# 8x2AND_OR_1.net
KiCad netlist of a schematic drawn in EAGLE
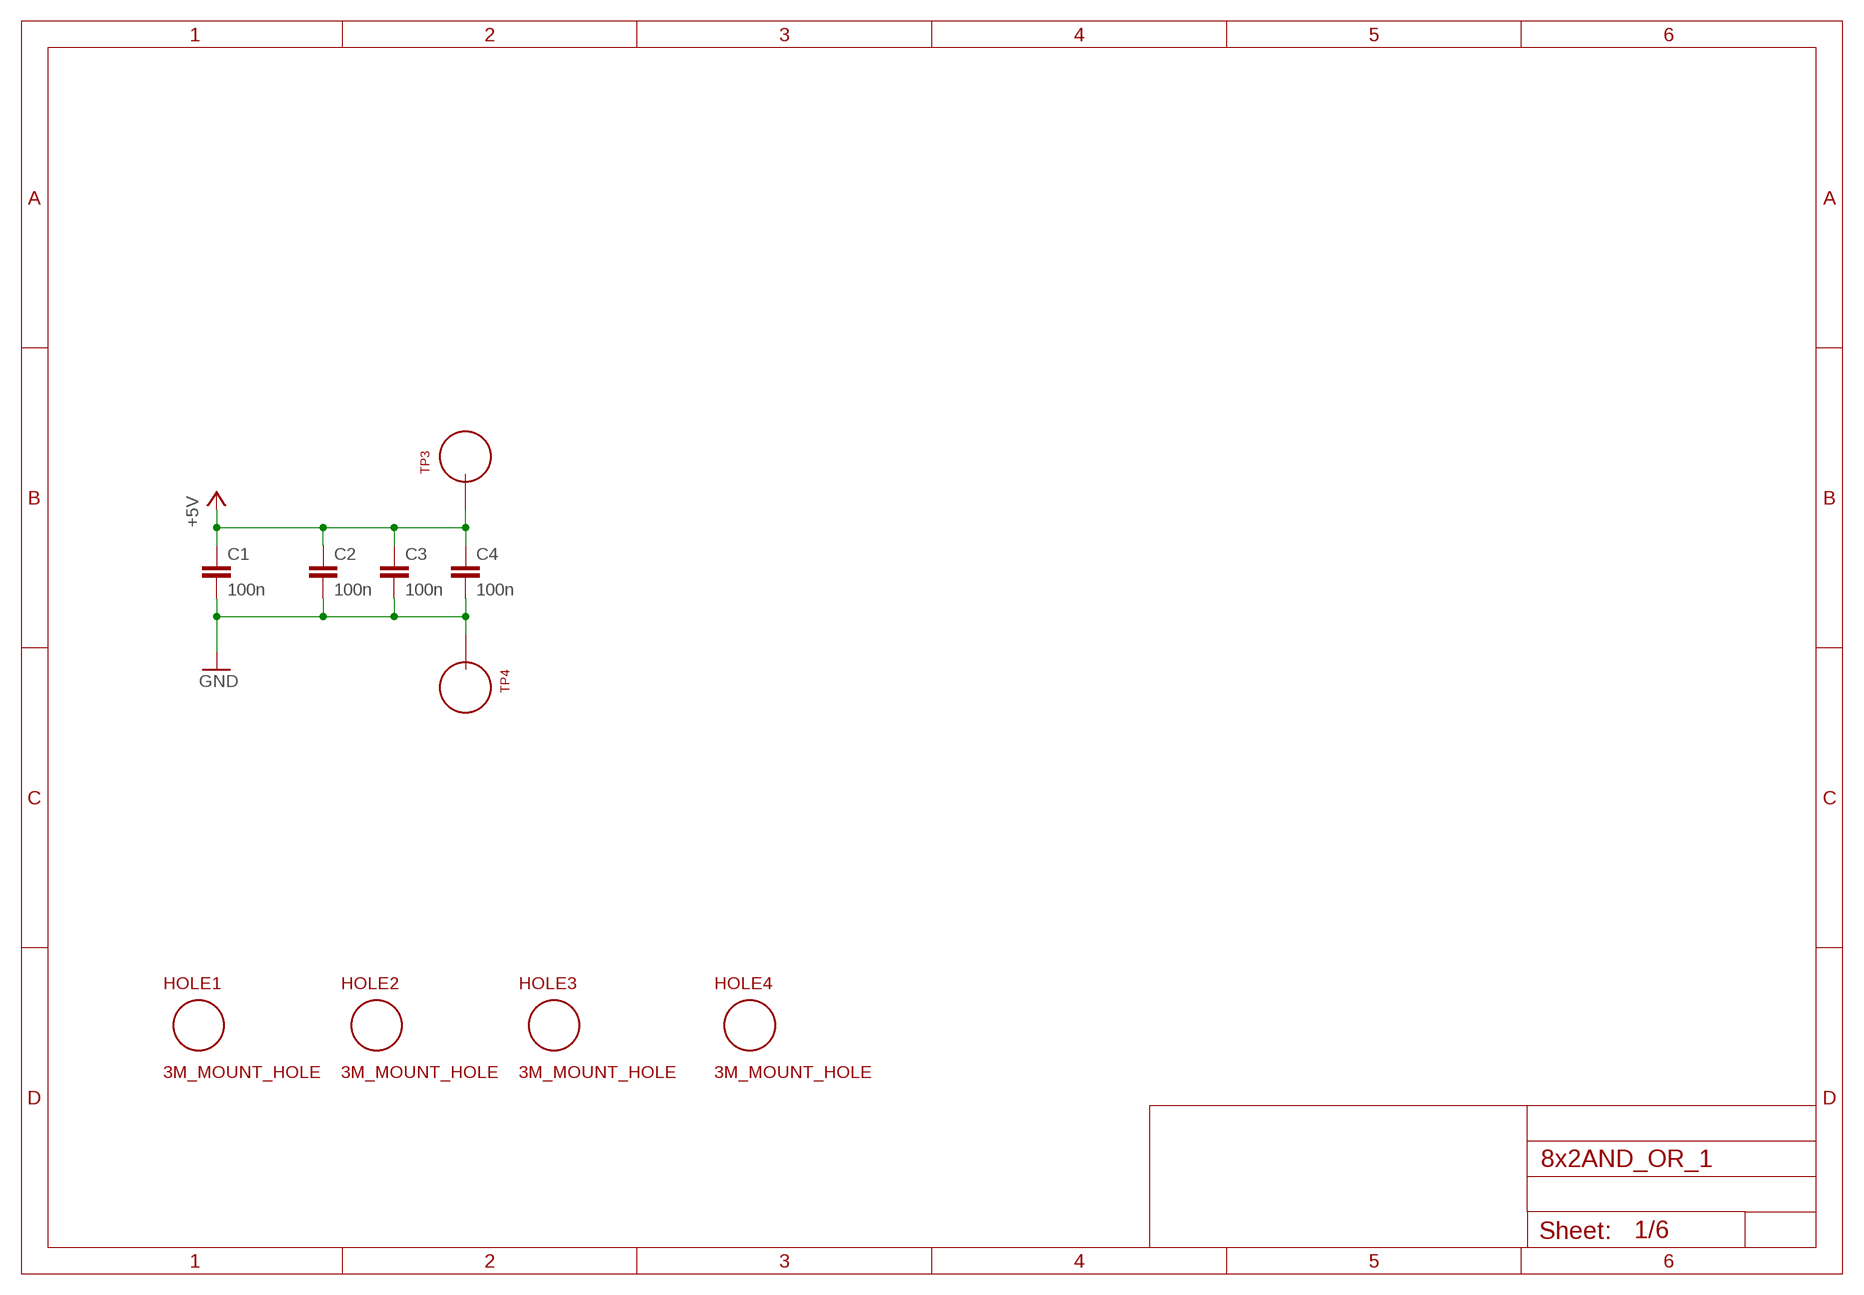
[diagram p0: schematic, sheet 1]
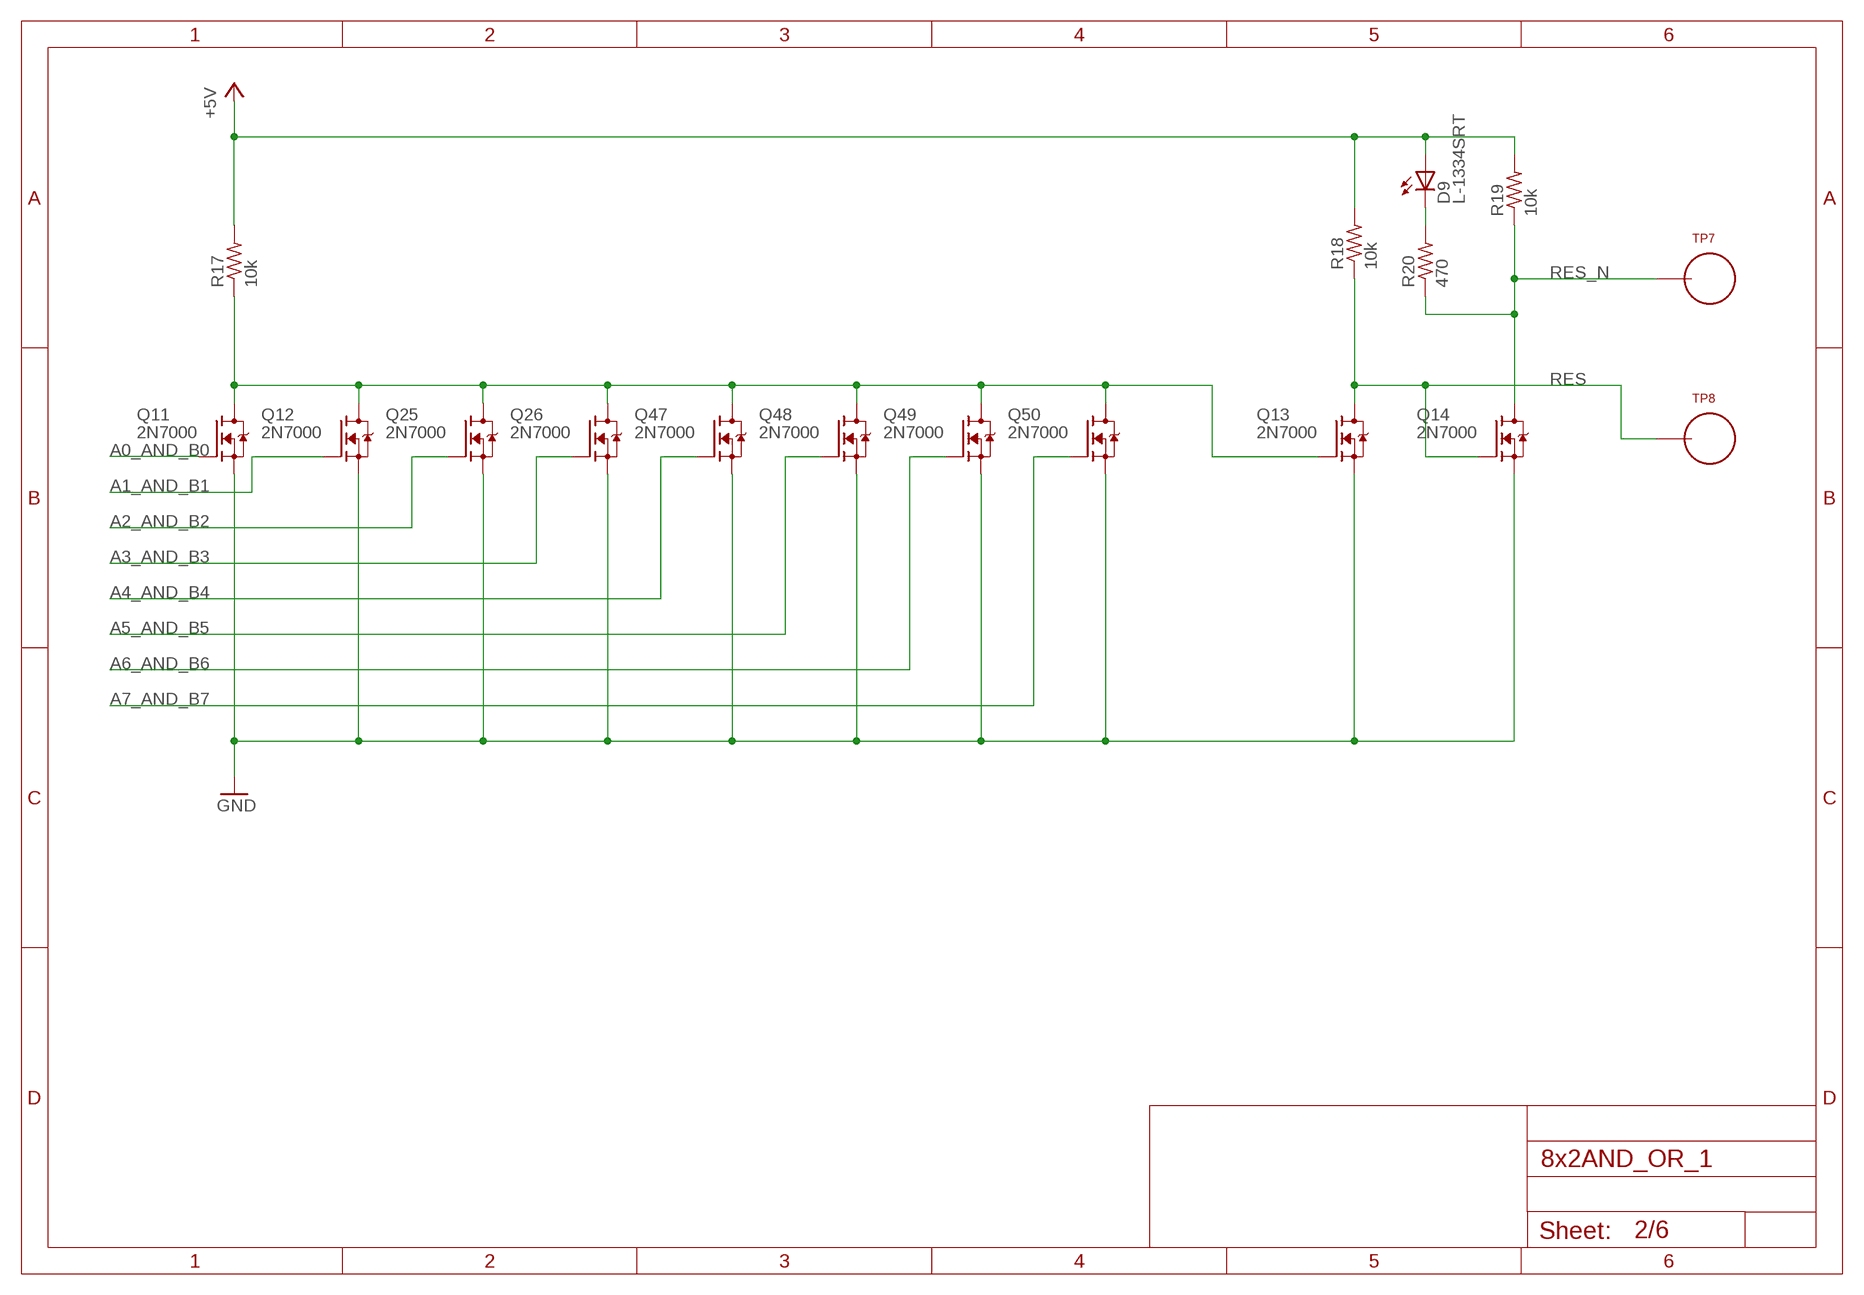
[diagram p1: schematic, sheet 2]
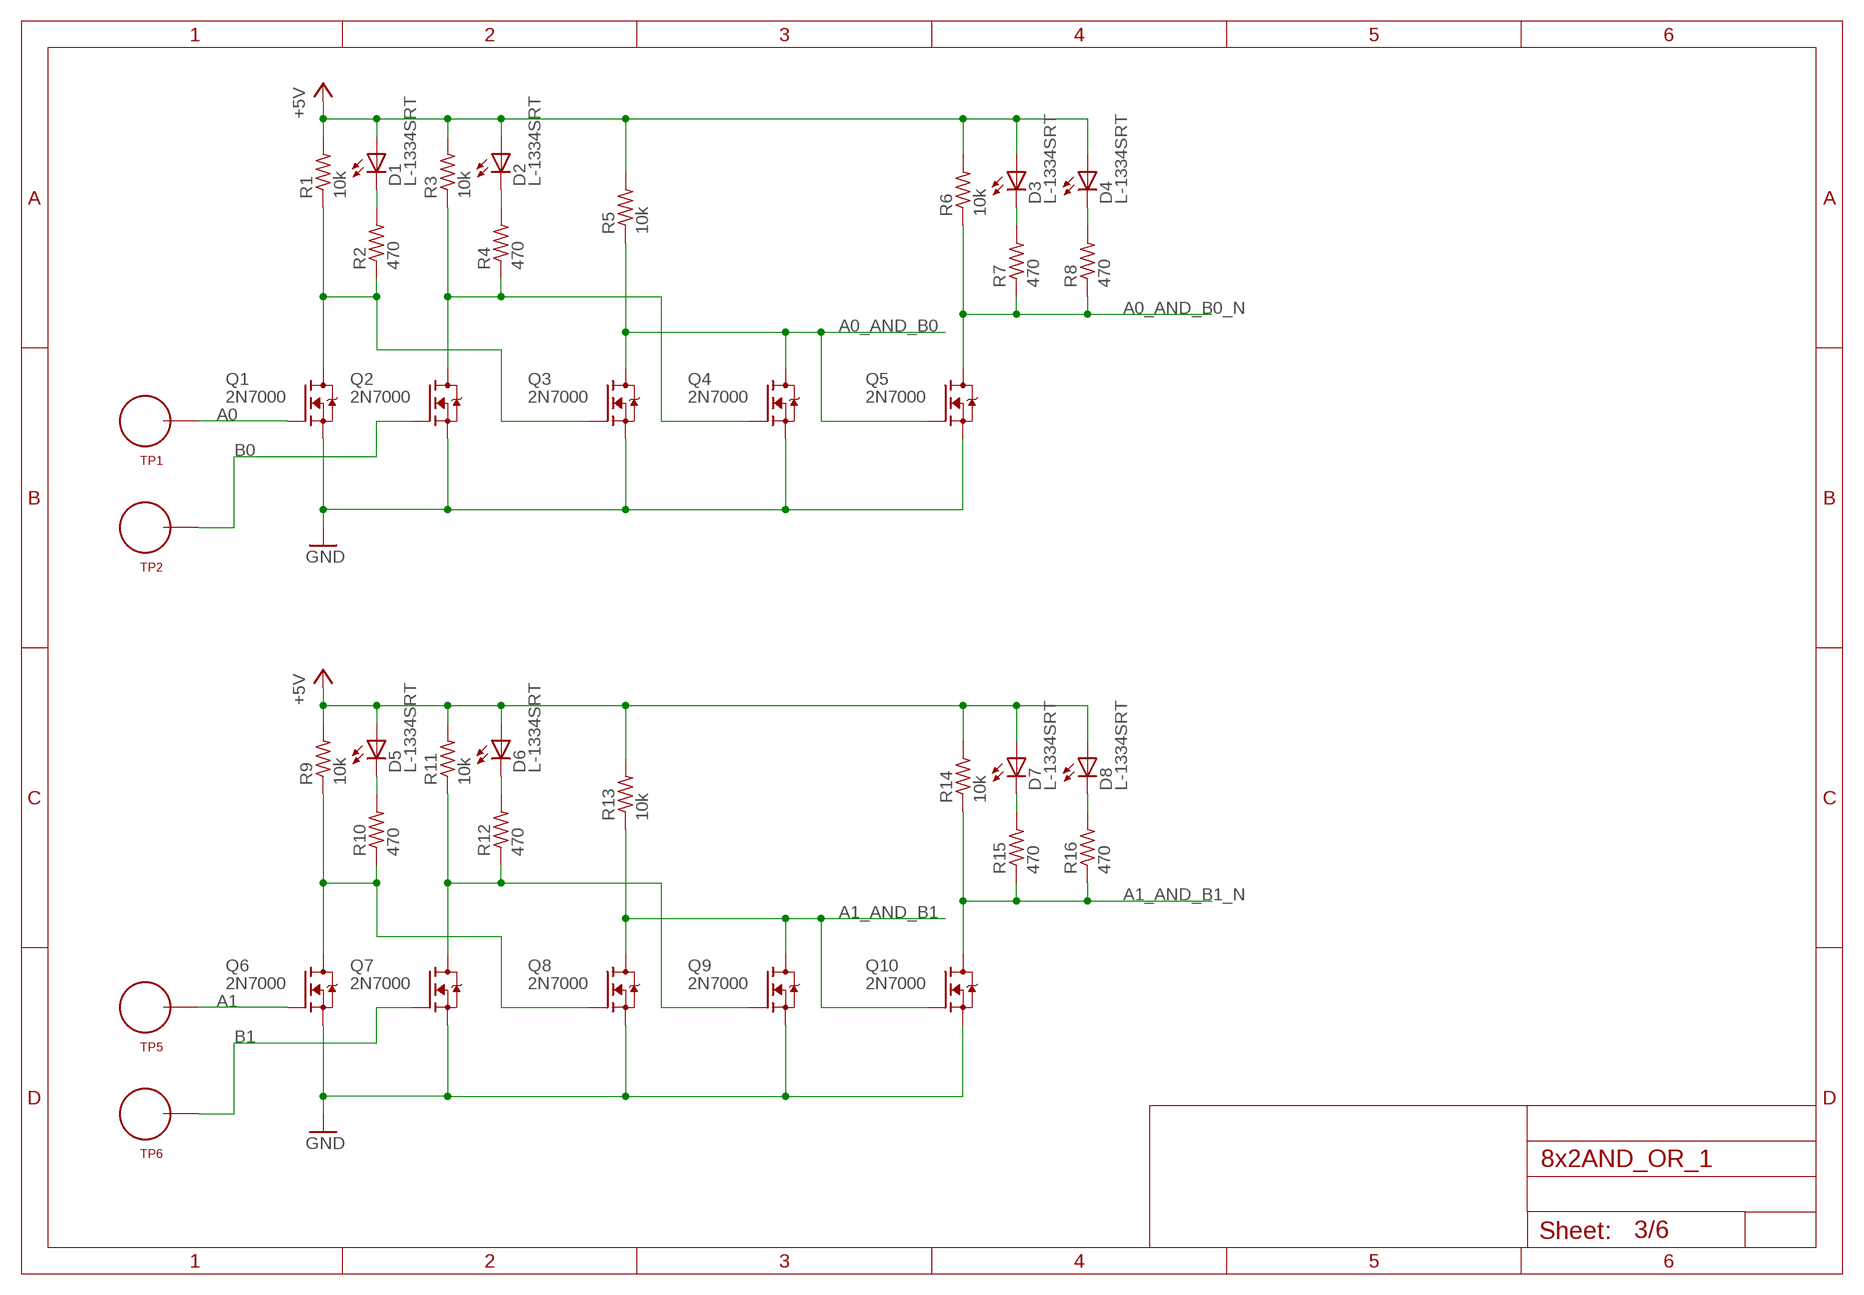
[diagram p2: schematic, sheet 3]
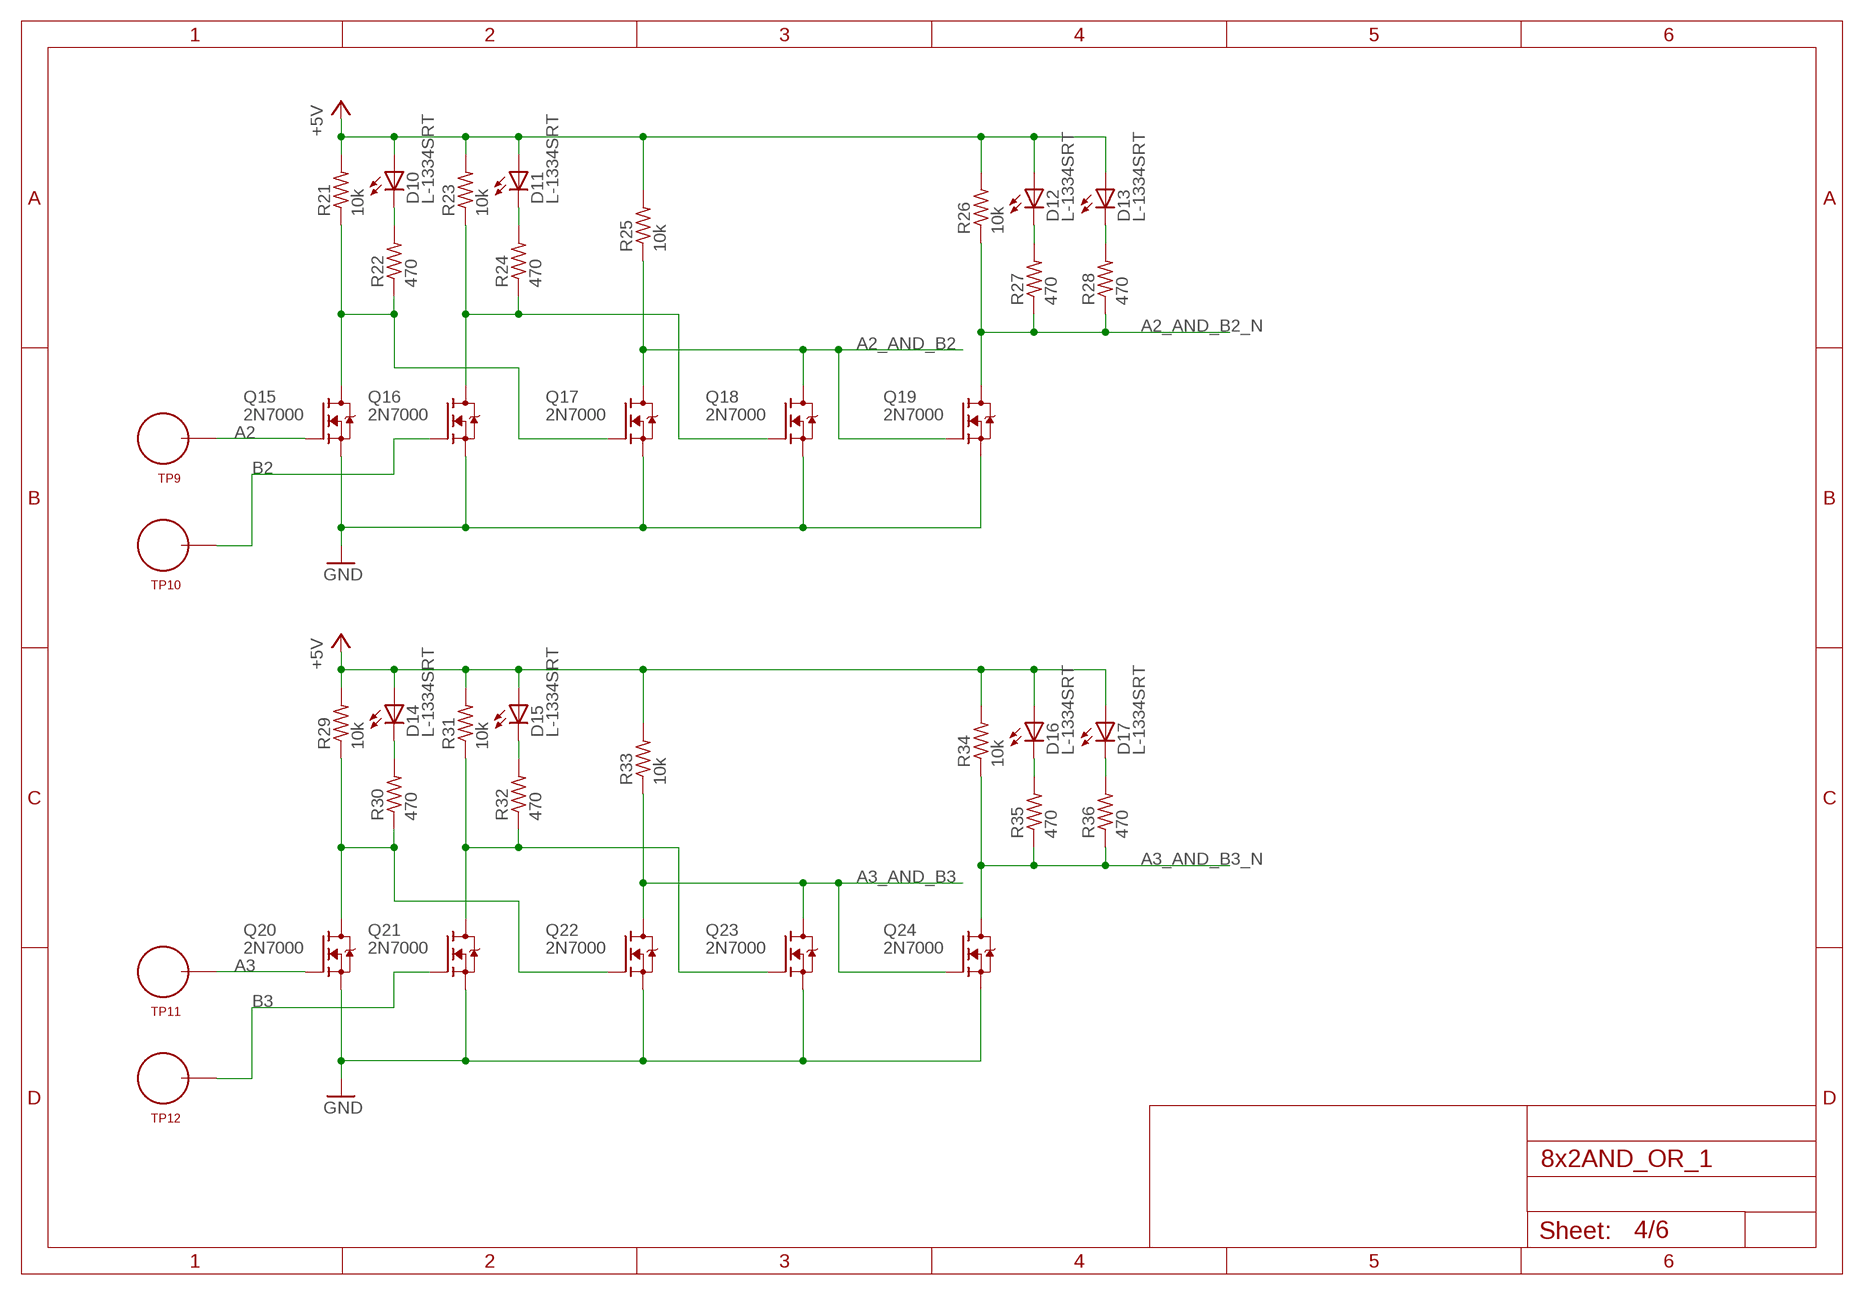
[diagram p3: schematic, sheet 4]
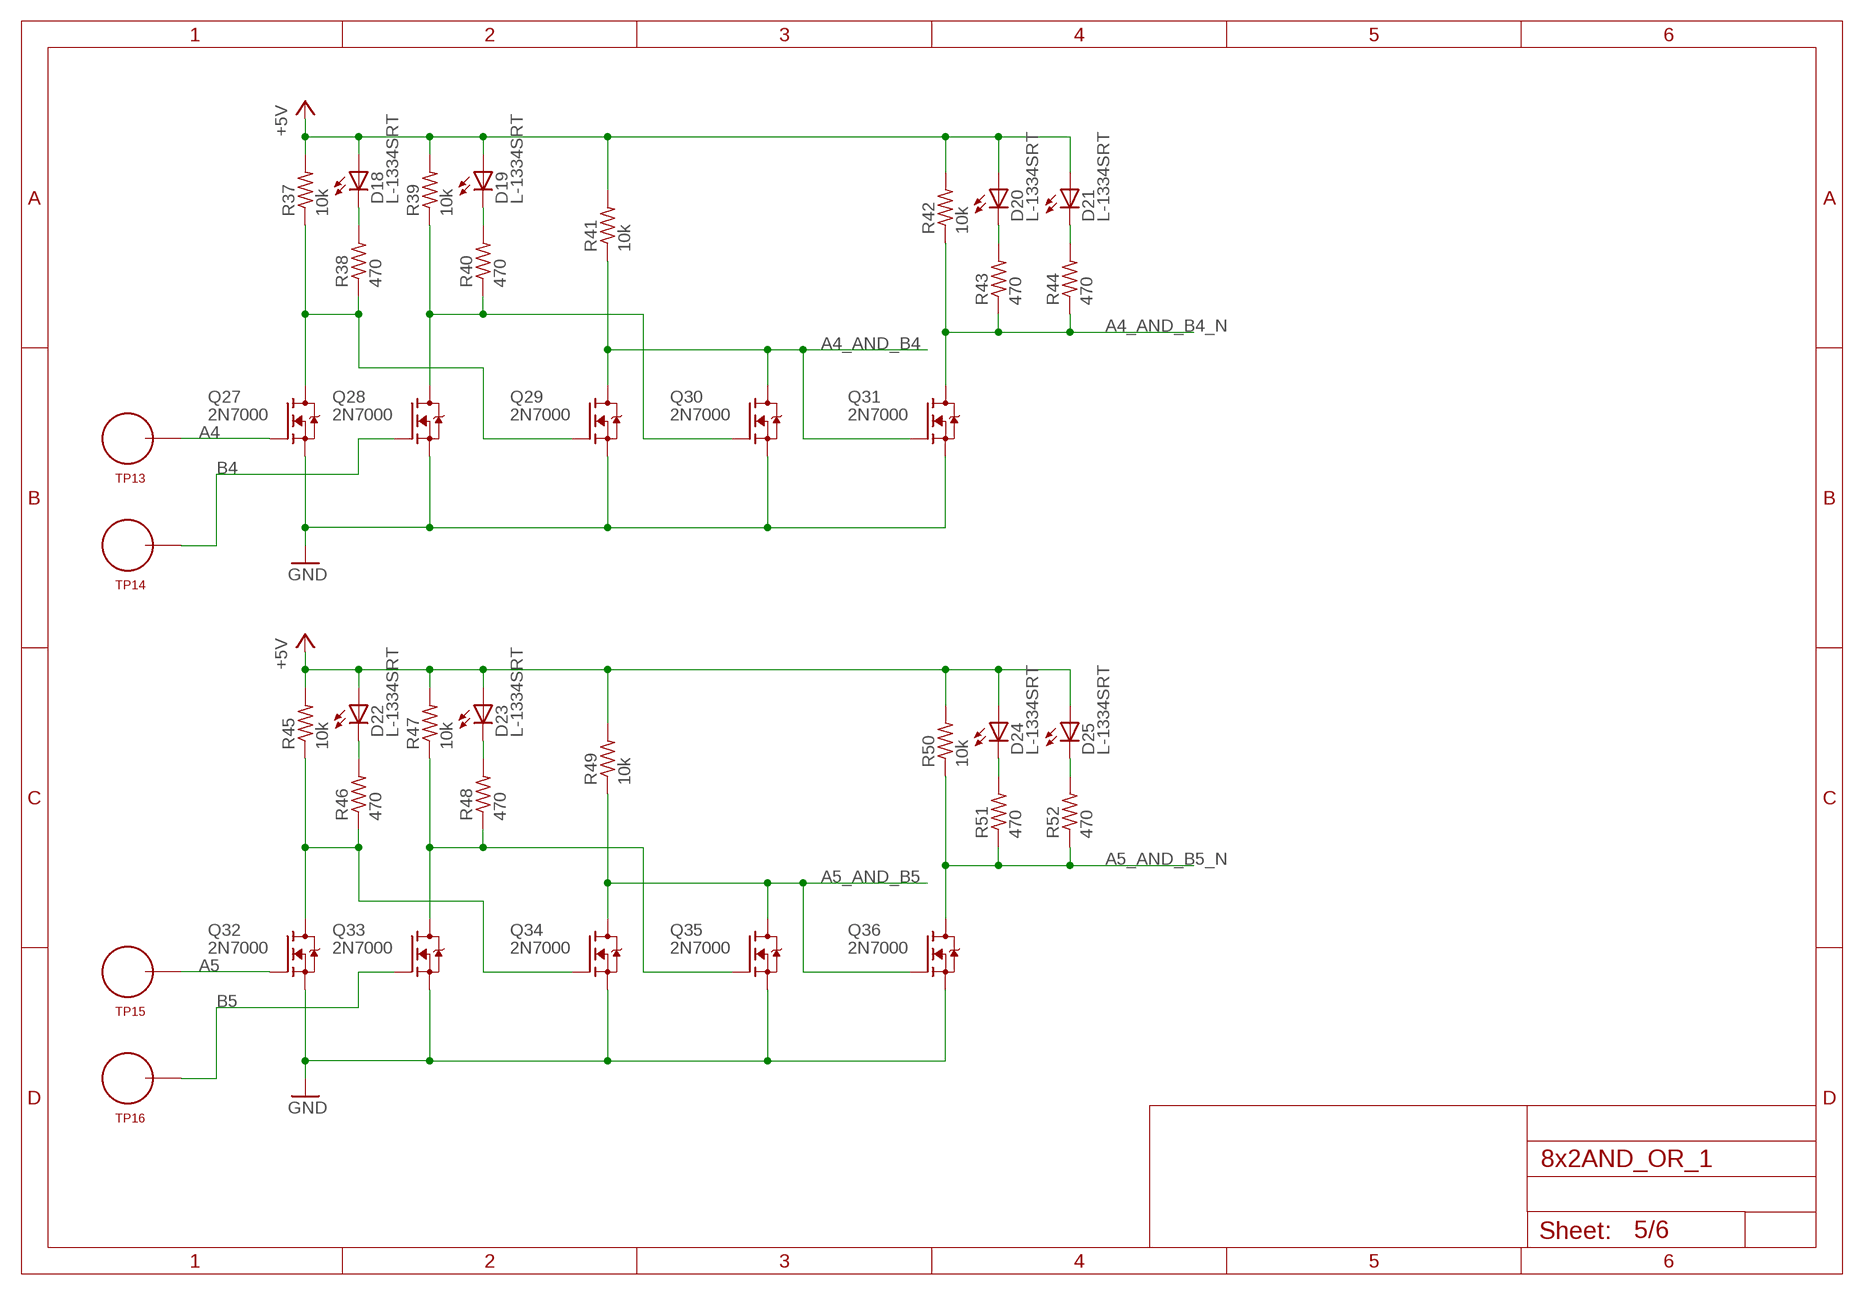
[diagram p4: schematic, sheet 5]
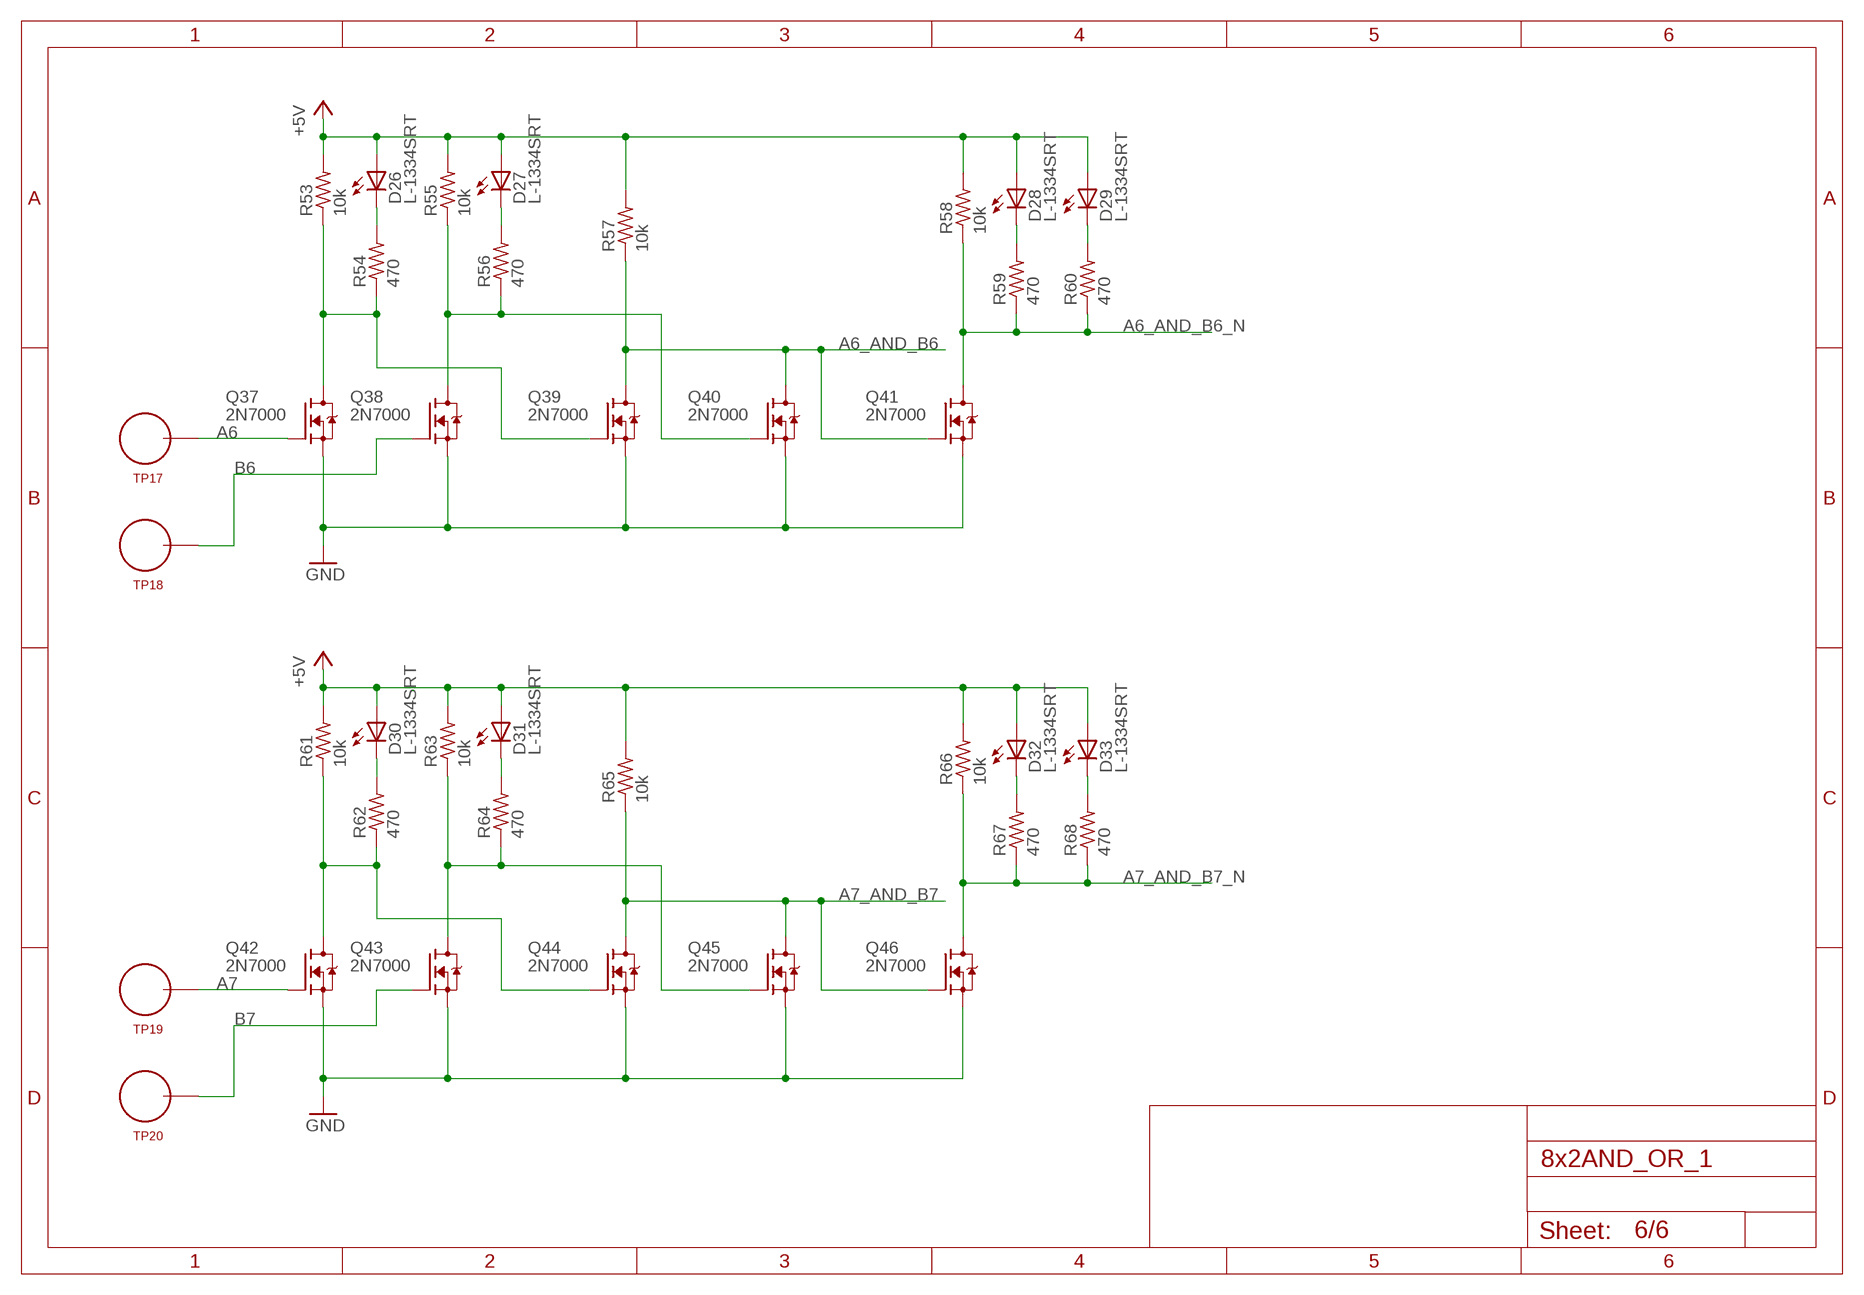
[diagram p5: schematic, sheet 6]

(export (version "E")
  (design (tool "Eeschema 10.0.6"))
  (components
    (comp (ref "D18")
      (value "L-1334SRT")
      (footprint "eagle-import:LED3MM")
      (libsource (lib "eagle-import") (part "L-1334SRT"))
    )
    (comp (ref "D19")
      (value "L-1334SRT")
      (footprint "eagle-import:LED3MM")
      (libsource (lib "eagle-import") (part "L-1334SRT"))
    )
    (comp (ref "D20")
      (value "L-1334SRT")
      (footprint "eagle-import:LED3MM")
      (libsource (lib "eagle-import") (part "L-1334SRT"))
    )
    (comp (ref "D21")
      (value "L-1334SRT")
      (footprint "eagle-import:LED3MM")
      (libsource (lib "eagle-import") (part "L-1334SRT"))
    )
    (comp (ref "D22")
      (value "L-1334SRT")
      (footprint "eagle-import:LED3MM")
      (libsource (lib "eagle-import") (part "L-1334SRT"))
    )
    (comp (ref "D23")
      (value "L-1334SRT")
      (footprint "eagle-import:LED3MM")
      (libsource (lib "eagle-import") (part "L-1334SRT"))
    )
    (comp (ref "D24")
      (value "L-1334SRT")
      (footprint "eagle-import:LED3MM")
      (libsource (lib "eagle-import") (part "L-1334SRT"))
    )
    (comp (ref "D25")
      (value "L-1334SRT")
      (footprint "eagle-import:LED3MM")
      (libsource (lib "eagle-import") (part "L-1334SRT"))
    )
    (comp (ref "Q27")
      (value "2N7000")
      (footprint "eagle-import:TO92-DGS")
      (libsource (lib "eagle-import") (part "2N7000"))
    )
    (comp (ref "Q28")
      (value "2N7000")
      (footprint "eagle-import:TO92-DGS")
      (libsource (lib "eagle-import") (part "2N7000"))
    )
    (comp (ref "Q29")
      (value "2N7000")
      (footprint "eagle-import:TO92-DGS")
      (libsource (lib "eagle-import") (part "2N7000"))
    )
    (comp (ref "Q30")
      (value "2N7000")
      (footprint "eagle-import:TO92-DGS")
      (libsource (lib "eagle-import") (part "2N7000"))
    )
    (comp (ref "Q31")
      (value "2N7000")
      (footprint "eagle-import:TO92-DGS")
      (libsource (lib "eagle-import") (part "2N7000"))
    )
    (comp (ref "Q32")
      (value "2N7000")
      (footprint "eagle-import:TO92-DGS")
      (libsource (lib "eagle-import") (part "2N7000"))
    )
    (comp (ref "Q33")
      (value "2N7000")
      (footprint "eagle-import:TO92-DGS")
      (libsource (lib "eagle-import") (part "2N7000"))
    )
    (comp (ref "Q34")
      (value "2N7000")
      (footprint "eagle-import:TO92-DGS")
      (libsource (lib "eagle-import") (part "2N7000"))
    )
    (comp (ref "Q35")
      (value "2N7000")
      (footprint "eagle-import:TO92-DGS")
      (libsource (lib "eagle-import") (part "2N7000"))
    )
    (comp (ref "Q36")
      (value "2N7000")
      (footprint "eagle-import:TO92-DGS")
      (libsource (lib "eagle-import") (part "2N7000"))
    )
    (comp (ref "R37")
      (value "10k")
      (footprint "eagle-import:R_P2INCH")
      (libsource (lib "eagle-import") (part "R_P2INCH"))
    )
    (comp (ref "R38")
      (value "470")
      (footprint "eagle-import:R_P2INCH")
      (libsource (lib "eagle-import") (part "R_P2INCH"))
    )
    (comp (ref "R39")
      (value "10k")
      (footprint "eagle-import:R_P2INCH")
      (libsource (lib "eagle-import") (part "R_P2INCH"))
    )
    (comp (ref "R40")
      (value "470")
      (footprint "eagle-import:R_P2INCH")
      (libsource (lib "eagle-import") (part "R_P2INCH"))
    )
    (comp (ref "R41")
      (value "10k")
      (footprint "eagle-import:R_P2INCH")
      (libsource (lib "eagle-import") (part "R_P2INCH"))
    )
    (comp (ref "R42")
      (value "10k")
      (footprint "eagle-import:R_P2INCH")
      (libsource (lib "eagle-import") (part "R_P2INCH"))
    )
    (comp (ref "R43")
      (value "470")
      (footprint "eagle-import:R_P2INCH")
      (libsource (lib "eagle-import") (part "R_P2INCH"))
    )
    (comp (ref "R44")
      (value "470")
      (footprint "eagle-import:R_P2INCH")
      (libsource (lib "eagle-import") (part "R_P2INCH"))
    )
    (comp (ref "R45")
      (value "10k")
      (footprint "eagle-import:R_P2INCH")
      (libsource (lib "eagle-import") (part "R_P2INCH"))
    )
    (comp (ref "R46")
      (value "470")
      (footprint "eagle-import:R_P2INCH")
      (libsource (lib "eagle-import") (part "R_P2INCH"))
    )
    (comp (ref "R47")
      (value "10k")
      (footprint "eagle-import:R_P2INCH")
      (libsource (lib "eagle-import") (part "R_P2INCH"))
    )
    (comp (ref "R48")
      (value "470")
      (footprint "eagle-import:R_P2INCH")
      (libsource (lib "eagle-import") (part "R_P2INCH"))
    )
    (comp (ref "R49")
      (value "10k")
      (footprint "eagle-import:R_P2INCH")
      (libsource (lib "eagle-import") (part "R_P2INCH"))
    )
    (comp (ref "R50")
      (value "10k")
      (footprint "eagle-import:R_P2INCH")
      (libsource (lib "eagle-import") (part "R_P2INCH"))
    )
    (comp (ref "R51")
      (value "470")
      (footprint "eagle-import:R_P2INCH")
      (libsource (lib "eagle-import") (part "R_P2INCH"))
    )
    (comp (ref "R52")
      (value "470")
      (footprint "eagle-import:R_P2INCH")
      (libsource (lib "eagle-import") (part "R_P2INCH"))
    )
    (comp (ref "TP13")
      (value "TEST_LOOP")
      (footprint "eagle-import:TEST_LOOP")
      (libsource (lib "eagle-import") (part "TEST_LOOP"))
    )
    (comp (ref "TP14")
      (value "TEST_LOOP")
      (footprint "eagle-import:TEST_LOOP")
      (libsource (lib "eagle-import") (part "TEST_LOOP"))
    )
    (comp (ref "TP15")
      (value "TEST_LOOP")
      (footprint "eagle-import:TEST_LOOP")
      (libsource (lib "eagle-import") (part "TEST_LOOP"))
    )
    (comp (ref "TP16")
      (value "TEST_LOOP")
      (footprint "eagle-import:TEST_LOOP")
      (libsource (lib "eagle-import") (part "TEST_LOOP"))
    )
    (comp (ref "D9")
      (value "L-1334SRT")
      (footprint "eagle-import:LED3MM")
      (libsource (lib "eagle-import") (part "L-1334SRT"))
    )
    (comp (ref "Q11")
      (value "2N7000")
      (footprint "eagle-import:TO92-DGS")
      (libsource (lib "eagle-import") (part "2N7000"))
    )
    (comp (ref "Q12")
      (value "2N7000")
      (footprint "eagle-import:TO92-DGS")
      (libsource (lib "eagle-import") (part "2N7000"))
    )
    (comp (ref "Q13")
      (value "2N7000")
      (footprint "eagle-import:TO92-DGS")
      (libsource (lib "eagle-import") (part "2N7000"))
    )
    (comp (ref "Q14")
      (value "2N7000")
      (footprint "eagle-import:TO92-DGS")
      (libsource (lib "eagle-import") (part "2N7000"))
    )
    (comp (ref "Q25")
      (value "2N7000")
      (footprint "eagle-import:TO92-DGS")
      (libsource (lib "eagle-import") (part "2N7000"))
    )
    (comp (ref "Q26")
      (value "2N7000")
      (footprint "eagle-import:TO92-DGS")
      (libsource (lib "eagle-import") (part "2N7000"))
    )
    (comp (ref "Q47")
      (value "2N7000")
      (footprint "eagle-import:TO92-DGS")
      (libsource (lib "eagle-import") (part "2N7000"))
    )
    (comp (ref "Q48")
      (value "2N7000")
      (footprint "eagle-import:TO92-DGS")
      (libsource (lib "eagle-import") (part "2N7000"))
    )
    (comp (ref "Q49")
      (value "2N7000")
      (footprint "eagle-import:TO92-DGS")
      (libsource (lib "eagle-import") (part "2N7000"))
    )
    (comp (ref "Q50")
      (value "2N7000")
      (footprint "eagle-import:TO92-DGS")
      (libsource (lib "eagle-import") (part "2N7000"))
    )
    (comp (ref "R17")
      (value "10k")
      (footprint "eagle-import:R_P2INCH")
      (libsource (lib "eagle-import") (part "R_P2INCH"))
    )
    (comp (ref "R18")
      (value "10k")
      (footprint "eagle-import:R_P2INCH")
      (libsource (lib "eagle-import") (part "R_P2INCH"))
    )
    (comp (ref "R19")
      (value "10k")
      (footprint "eagle-import:R_P2INCH")
      (libsource (lib "eagle-import") (part "R_P2INCH"))
    )
    (comp (ref "R20")
      (value "470")
      (footprint "eagle-import:R_P2INCH")
      (libsource (lib "eagle-import") (part "R_P2INCH"))
    )
    (comp (ref "TP7")
      (value "TEST_LOOP")
      (footprint "eagle-import:TEST_LOOP")
      (libsource (lib "eagle-import") (part "TEST_LOOP"))
    )
    (comp (ref "TP8")
      (value "TEST_LOOP")
      (footprint "eagle-import:TEST_LOOP")
      (libsource (lib "eagle-import") (part "TEST_LOOP"))
    )
    (comp (ref "D10")
      (value "L-1334SRT")
      (footprint "eagle-import:LED3MM")
      (libsource (lib "eagle-import") (part "L-1334SRT"))
    )
    (comp (ref "D11")
      (value "L-1334SRT")
      (footprint "eagle-import:LED3MM")
      (libsource (lib "eagle-import") (part "L-1334SRT"))
    )
    (comp (ref "D12")
      (value "L-1334SRT")
      (footprint "eagle-import:LED3MM")
      (libsource (lib "eagle-import") (part "L-1334SRT"))
    )
    (comp (ref "D13")
      (value "L-1334SRT")
      (footprint "eagle-import:LED3MM")
      (libsource (lib "eagle-import") (part "L-1334SRT"))
    )
    (comp (ref "D14")
      (value "L-1334SRT")
      (footprint "eagle-import:LED3MM")
      (libsource (lib "eagle-import") (part "L-1334SRT"))
    )
    (comp (ref "D15")
      (value "L-1334SRT")
      (footprint "eagle-import:LED3MM")
      (libsource (lib "eagle-import") (part "L-1334SRT"))
    )
    (comp (ref "D16")
      (value "L-1334SRT")
      (footprint "eagle-import:LED3MM")
      (libsource (lib "eagle-import") (part "L-1334SRT"))
    )
    (comp (ref "D17")
      (value "L-1334SRT")
      (footprint "eagle-import:LED3MM")
      (libsource (lib "eagle-import") (part "L-1334SRT"))
    )
    (comp (ref "Q15")
      (value "2N7000")
      (footprint "eagle-import:TO92-DGS")
      (libsource (lib "eagle-import") (part "2N7000"))
    )
    (comp (ref "Q16")
      (value "2N7000")
      (footprint "eagle-import:TO92-DGS")
      (libsource (lib "eagle-import") (part "2N7000"))
    )
    (comp (ref "Q17")
      (value "2N7000")
      (footprint "eagle-import:TO92-DGS")
      (libsource (lib "eagle-import") (part "2N7000"))
    )
    (comp (ref "Q18")
      (value "2N7000")
      (footprint "eagle-import:TO92-DGS")
      (libsource (lib "eagle-import") (part "2N7000"))
    )
    (comp (ref "Q19")
      (value "2N7000")
      (footprint "eagle-import:TO92-DGS")
      (libsource (lib "eagle-import") (part "2N7000"))
    )
    (comp (ref "Q20")
      (value "2N7000")
      (footprint "eagle-import:TO92-DGS")
      (libsource (lib "eagle-import") (part "2N7000"))
    )
    (comp (ref "Q21")
      (value "2N7000")
      (footprint "eagle-import:TO92-DGS")
      (libsource (lib "eagle-import") (part "2N7000"))
    )
    (comp (ref "Q22")
      (value "2N7000")
      (footprint "eagle-import:TO92-DGS")
      (libsource (lib "eagle-import") (part "2N7000"))
    )
    (comp (ref "Q23")
      (value "2N7000")
      (footprint "eagle-import:TO92-DGS")
      (libsource (lib "eagle-import") (part "2N7000"))
    )
    (comp (ref "Q24")
      (value "2N7000")
      (footprint "eagle-import:TO92-DGS")
      (libsource (lib "eagle-import") (part "2N7000"))
    )
    (comp (ref "R21")
      (value "10k")
      (footprint "eagle-import:R_P2INCH")
      (libsource (lib "eagle-import") (part "R_P2INCH"))
    )
    (comp (ref "R22")
      (value "470")
      (footprint "eagle-import:R_P2INCH")
      (libsource (lib "eagle-import") (part "R_P2INCH"))
    )
    (comp (ref "R23")
      (value "10k")
      (footprint "eagle-import:R_P2INCH")
      (libsource (lib "eagle-import") (part "R_P2INCH"))
    )
    (comp (ref "R24")
      (value "470")
      (footprint "eagle-import:R_P2INCH")
      (libsource (lib "eagle-import") (part "R_P2INCH"))
    )
    (comp (ref "R25")
      (value "10k")
      (footprint "eagle-import:R_P2INCH")
      (libsource (lib "eagle-import") (part "R_P2INCH"))
    )
    (comp (ref "R26")
      (value "10k")
      (footprint "eagle-import:R_P2INCH")
      (libsource (lib "eagle-import") (part "R_P2INCH"))
    )
    (comp (ref "R27")
      (value "470")
      (footprint "eagle-import:R_P2INCH")
      (libsource (lib "eagle-import") (part "R_P2INCH"))
    )
    (comp (ref "R28")
      (value "470")
      (footprint "eagle-import:R_P2INCH")
      (libsource (lib "eagle-import") (part "R_P2INCH"))
    )
    (comp (ref "R29")
      (value "10k")
      (footprint "eagle-import:R_P2INCH")
      (libsource (lib "eagle-import") (part "R_P2INCH"))
    )
    (comp (ref "R30")
      (value "470")
      (footprint "eagle-import:R_P2INCH")
      (libsource (lib "eagle-import") (part "R_P2INCH"))
    )
    (comp (ref "R31")
      (value "10k")
      (footprint "eagle-import:R_P2INCH")
      (libsource (lib "eagle-import") (part "R_P2INCH"))
    )
    (comp (ref "R32")
      (value "470")
      (footprint "eagle-import:R_P2INCH")
      (libsource (lib "eagle-import") (part "R_P2INCH"))
    )
    (comp (ref "R33")
      (value "10k")
      (footprint "eagle-import:R_P2INCH")
      (libsource (lib "eagle-import") (part "R_P2INCH"))
    )
    (comp (ref "R34")
      (value "10k")
      (footprint "eagle-import:R_P2INCH")
      (libsource (lib "eagle-import") (part "R_P2INCH"))
    )
    (comp (ref "R35")
      (value "470")
      (footprint "eagle-import:R_P2INCH")
      (libsource (lib "eagle-import") (part "R_P2INCH"))
    )
    (comp (ref "R36")
      (value "470")
      (footprint "eagle-import:R_P2INCH")
      (libsource (lib "eagle-import") (part "R_P2INCH"))
    )
    (comp (ref "TP9")
      (value "TEST_LOOP")
      (footprint "eagle-import:TEST_LOOP")
      (libsource (lib "eagle-import") (part "TEST_LOOP"))
    )
    (comp (ref "TP10")
      (value "TEST_LOOP")
      (footprint "eagle-import:TEST_LOOP")
      (libsource (lib "eagle-import") (part "TEST_LOOP"))
    )
    (comp (ref "TP11")
      (value "TEST_LOOP")
      (footprint "eagle-import:TEST_LOOP")
      (libsource (lib "eagle-import") (part "TEST_LOOP"))
    )
    (comp (ref "TP12")
      (value "TEST_LOOP")
      (footprint "eagle-import:TEST_LOOP")
      (libsource (lib "eagle-import") (part "TEST_LOOP"))
    )
    (comp (ref "D1")
      (value "L-1334SRT")
      (footprint "eagle-import:LED3MM")
      (libsource (lib "eagle-import") (part "L-1334SRT"))
    )
    (comp (ref "D2")
      (value "L-1334SRT")
      (footprint "eagle-import:LED3MM")
      (libsource (lib "eagle-import") (part "L-1334SRT"))
    )
    (comp (ref "D3")
      (value "L-1334SRT")
      (footprint "eagle-import:LED3MM")
      (libsource (lib "eagle-import") (part "L-1334SRT"))
    )
    (comp (ref "D4")
      (value "L-1334SRT")
      (footprint "eagle-import:LED3MM")
      (libsource (lib "eagle-import") (part "L-1334SRT"))
    )
    (comp (ref "D5")
      (value "L-1334SRT")
      (footprint "eagle-import:LED3MM")
      (libsource (lib "eagle-import") (part "L-1334SRT"))
    )
    (comp (ref "D6")
      (value "L-1334SRT")
      (footprint "eagle-import:LED3MM")
      (libsource (lib "eagle-import") (part "L-1334SRT"))
    )
    (comp (ref "D7")
      (value "L-1334SRT")
      (footprint "eagle-import:LED3MM")
      (libsource (lib "eagle-import") (part "L-1334SRT"))
    )
    (comp (ref "D8")
      (value "L-1334SRT")
      (footprint "eagle-import:LED3MM")
      (libsource (lib "eagle-import") (part "L-1334SRT"))
    )
    (comp (ref "Q1")
      (value "2N7000")
      (footprint "eagle-import:TO92-DGS")
      (libsource (lib "eagle-import") (part "2N7000"))
    )
    (comp (ref "Q2")
      (value "2N7000")
      (footprint "eagle-import:TO92-DGS")
      (libsource (lib "eagle-import") (part "2N7000"))
    )
    (comp (ref "Q3")
      (value "2N7000")
      (footprint "eagle-import:TO92-DGS")
      (libsource (lib "eagle-import") (part "2N7000"))
    )
    (comp (ref "Q4")
      (value "2N7000")
      (footprint "eagle-import:TO92-DGS")
      (libsource (lib "eagle-import") (part "2N7000"))
    )
    (comp (ref "Q5")
      (value "2N7000")
      (footprint "eagle-import:TO92-DGS")
      (libsource (lib "eagle-import") (part "2N7000"))
    )
    (comp (ref "Q6")
      (value "2N7000")
      (footprint "eagle-import:TO92-DGS")
      (libsource (lib "eagle-import") (part "2N7000"))
    )
    (comp (ref "Q7")
      (value "2N7000")
      (footprint "eagle-import:TO92-DGS")
      (libsource (lib "eagle-import") (part "2N7000"))
    )
    (comp (ref "Q8")
      (value "2N7000")
      (footprint "eagle-import:TO92-DGS")
      (libsource (lib "eagle-import") (part "2N7000"))
    )
    (comp (ref "Q9")
      (value "2N7000")
      (footprint "eagle-import:TO92-DGS")
      (libsource (lib "eagle-import") (part "2N7000"))
    )
    (comp (ref "Q10")
      (value "2N7000")
      (footprint "eagle-import:TO92-DGS")
      (libsource (lib "eagle-import") (part "2N7000"))
    )
    (comp (ref "R1")
      (value "10k")
      (footprint "eagle-import:R_P2INCH")
      (libsource (lib "eagle-import") (part "R_P2INCH"))
    )
    (comp (ref "R2")
      (value "470")
      (footprint "eagle-import:R_P2INCH")
      (libsource (lib "eagle-import") (part "R_P2INCH"))
    )
    (comp (ref "R3")
      (value "10k")
      (footprint "eagle-import:R_P2INCH")
      (libsource (lib "eagle-import") (part "R_P2INCH"))
    )
    (comp (ref "R4")
      (value "470")
      (footprint "eagle-import:R_P2INCH")
      (libsource (lib "eagle-import") (part "R_P2INCH"))
    )
    (comp (ref "R5")
      (value "10k")
      (footprint "eagle-import:R_P2INCH")
      (libsource (lib "eagle-import") (part "R_P2INCH"))
    )
    (comp (ref "R6")
      (value "10k")
      (footprint "eagle-import:R_P2INCH")
      (libsource (lib "eagle-import") (part "R_P2INCH"))
    )
    (comp (ref "R7")
      (value "470")
      (footprint "eagle-import:R_P2INCH")
      (libsource (lib "eagle-import") (part "R_P2INCH"))
    )
    (comp (ref "R8")
      (value "470")
      (footprint "eagle-import:R_P2INCH")
      (libsource (lib "eagle-import") (part "R_P2INCH"))
    )
    (comp (ref "R9")
      (value "10k")
      (footprint "eagle-import:R_P2INCH")
      (libsource (lib "eagle-import") (part "R_P2INCH"))
    )
    (comp (ref "R10")
      (value "470")
      (footprint "eagle-import:R_P2INCH")
      (libsource (lib "eagle-import") (part "R_P2INCH"))
    )
    (comp (ref "R11")
      (value "10k")
      (footprint "eagle-import:R_P2INCH")
      (libsource (lib "eagle-import") (part "R_P2INCH"))
    )
    (comp (ref "R12")
      (value "470")
      (footprint "eagle-import:R_P2INCH")
      (libsource (lib "eagle-import") (part "R_P2INCH"))
    )
    (comp (ref "R13")
      (value "10k")
      (footprint "eagle-import:R_P2INCH")
      (libsource (lib "eagle-import") (part "R_P2INCH"))
    )
    (comp (ref "R14")
      (value "10k")
      (footprint "eagle-import:R_P2INCH")
      (libsource (lib "eagle-import") (part "R_P2INCH"))
    )
    (comp (ref "R15")
      (value "470")
      (footprint "eagle-import:R_P2INCH")
      (libsource (lib "eagle-import") (part "R_P2INCH"))
    )
    (comp (ref "R16")
      (value "470")
      (footprint "eagle-import:R_P2INCH")
      (libsource (lib "eagle-import") (part "R_P2INCH"))
    )
    (comp (ref "TP1")
      (value "TEST_LOOP")
      (footprint "eagle-import:TEST_LOOP")
      (libsource (lib "eagle-import") (part "TEST_LOOP"))
    )
    (comp (ref "TP2")
      (value "TEST_LOOP")
      (footprint "eagle-import:TEST_LOOP")
      (libsource (lib "eagle-import") (part "TEST_LOOP"))
    )
    (comp (ref "TP5")
      (value "TEST_LOOP")
      (footprint "eagle-import:TEST_LOOP")
      (libsource (lib "eagle-import") (part "TEST_LOOP"))
    )
    (comp (ref "TP6")
      (value "TEST_LOOP")
      (footprint "eagle-import:TEST_LOOP")
      (libsource (lib "eagle-import") (part "TEST_LOOP"))
    )
    (comp (ref "D26")
      (value "L-1334SRT")
      (footprint "eagle-import:LED3MM")
      (libsource (lib "eagle-import") (part "L-1334SRT"))
    )
    (comp (ref "D27")
      (value "L-1334SRT")
      (footprint "eagle-import:LED3MM")
      (libsource (lib "eagle-import") (part "L-1334SRT"))
    )
    (comp (ref "D28")
      (value "L-1334SRT")
      (footprint "eagle-import:LED3MM")
      (libsource (lib "eagle-import") (part "L-1334SRT"))
    )
    (comp (ref "D29")
      (value "L-1334SRT")
      (footprint "eagle-import:LED3MM")
      (libsource (lib "eagle-import") (part "L-1334SRT"))
    )
    (comp (ref "D30")
      (value "L-1334SRT")
      (footprint "eagle-import:LED3MM")
      (libsource (lib "eagle-import") (part "L-1334SRT"))
    )
    (comp (ref "D31")
      (value "L-1334SRT")
      (footprint "eagle-import:LED3MM")
      (libsource (lib "eagle-import") (part "L-1334SRT"))
    )
    (comp (ref "D32")
      (value "L-1334SRT")
      (footprint "eagle-import:LED3MM")
      (libsource (lib "eagle-import") (part "L-1334SRT"))
    )
    (comp (ref "D33")
      (value "L-1334SRT")
      (footprint "eagle-import:LED3MM")
      (libsource (lib "eagle-import") (part "L-1334SRT"))
    )
    (comp (ref "Q37")
      (value "2N7000")
      (footprint "eagle-import:TO92-DGS")
      (libsource (lib "eagle-import") (part "2N7000"))
    )
    (comp (ref "Q38")
      (value "2N7000")
      (footprint "eagle-import:TO92-DGS")
      (libsource (lib "eagle-import") (part "2N7000"))
    )
    (comp (ref "Q39")
      (value "2N7000")
      (footprint "eagle-import:TO92-DGS")
      (libsource (lib "eagle-import") (part "2N7000"))
    )
    (comp (ref "Q40")
      (value "2N7000")
      (footprint "eagle-import:TO92-DGS")
      (libsource (lib "eagle-import") (part "2N7000"))
    )
    (comp (ref "Q41")
      (value "2N7000")
      (footprint "eagle-import:TO92-DGS")
      (libsource (lib "eagle-import") (part "2N7000"))
    )
    (comp (ref "Q42")
      (value "2N7000")
      (footprint "eagle-import:TO92-DGS")
      (libsource (lib "eagle-import") (part "2N7000"))
    )
    (comp (ref "Q43")
      (value "2N7000")
      (footprint "eagle-import:TO92-DGS")
      (libsource (lib "eagle-import") (part "2N7000"))
    )
    (comp (ref "Q44")
      (value "2N7000")
      (footprint "eagle-import:TO92-DGS")
      (libsource (lib "eagle-import") (part "2N7000"))
    )
    (comp (ref "Q45")
      (value "2N7000")
      (footprint "eagle-import:TO92-DGS")
      (libsource (lib "eagle-import") (part "2N7000"))
    )
    (comp (ref "Q46")
      (value "2N7000")
      (footprint "eagle-import:TO92-DGS")
      (libsource (lib "eagle-import") (part "2N7000"))
    )
    (comp (ref "R53")
      (value "10k")
      (footprint "eagle-import:R_P2INCH")
      (libsource (lib "eagle-import") (part "R_P2INCH"))
    )
    (comp (ref "R54")
      (value "470")
      (footprint "eagle-import:R_P2INCH")
      (libsource (lib "eagle-import") (part "R_P2INCH"))
    )
    (comp (ref "R55")
      (value "10k")
      (footprint "eagle-import:R_P2INCH")
      (libsource (lib "eagle-import") (part "R_P2INCH"))
    )
    (comp (ref "R56")
      (value "470")
      (footprint "eagle-import:R_P2INCH")
      (libsource (lib "eagle-import") (part "R_P2INCH"))
    )
    (comp (ref "R57")
      (value "10k")
      (footprint "eagle-import:R_P2INCH")
      (libsource (lib "eagle-import") (part "R_P2INCH"))
    )
    (comp (ref "R58")
      (value "10k")
      (footprint "eagle-import:R_P2INCH")
      (libsource (lib "eagle-import") (part "R_P2INCH"))
    )
    (comp (ref "R59")
      (value "470")
      (footprint "eagle-import:R_P2INCH")
      (libsource (lib "eagle-import") (part "R_P2INCH"))
    )
    (comp (ref "R60")
      (value "470")
      (footprint "eagle-import:R_P2INCH")
      (libsource (lib "eagle-import") (part "R_P2INCH"))
    )
    (comp (ref "R61")
      (value "10k")
      (footprint "eagle-import:R_P2INCH")
      (libsource (lib "eagle-import") (part "R_P2INCH"))
    )
    (comp (ref "R62")
      (value "470")
      (footprint "eagle-import:R_P2INCH")
      (libsource (lib "eagle-import") (part "R_P2INCH"))
    )
    (comp (ref "R63")
      (value "10k")
      (footprint "eagle-import:R_P2INCH")
      (libsource (lib "eagle-import") (part "R_P2INCH"))
    )
    (comp (ref "R64")
      (value "470")
      (footprint "eagle-import:R_P2INCH")
      (libsource (lib "eagle-import") (part "R_P2INCH"))
    )
    (comp (ref "R65")
      (value "10k")
      (footprint "eagle-import:R_P2INCH")
      (libsource (lib "eagle-import") (part "R_P2INCH"))
    )
    (comp (ref "R66")
      (value "10k")
      (footprint "eagle-import:R_P2INCH")
      (libsource (lib "eagle-import") (part "R_P2INCH"))
    )
    (comp (ref "R67")
      (value "470")
      (footprint "eagle-import:R_P2INCH")
      (libsource (lib "eagle-import") (part "R_P2INCH"))
    )
    (comp (ref "R68")
      (value "470")
      (footprint "eagle-import:R_P2INCH")
      (libsource (lib "eagle-import") (part "R_P2INCH"))
    )
    (comp (ref "TP17")
      (value "TEST_LOOP")
      (footprint "eagle-import:TEST_LOOP")
      (libsource (lib "eagle-import") (part "TEST_LOOP"))
    )
    (comp (ref "TP18")
      (value "TEST_LOOP")
      (footprint "eagle-import:TEST_LOOP")
      (libsource (lib "eagle-import") (part "TEST_LOOP"))
    )
    (comp (ref "TP19")
      (value "TEST_LOOP")
      (footprint "eagle-import:TEST_LOOP")
      (libsource (lib "eagle-import") (part "TEST_LOOP"))
    )
    (comp (ref "TP20")
      (value "TEST_LOOP")
      (footprint "eagle-import:TEST_LOOP")
      (libsource (lib "eagle-import") (part "TEST_LOOP"))
    )
    (comp (ref "C1")
      (value "100n")
      (footprint "eagle-import:CAP_P2INCH")
      (libsource (lib "eagle-import") (part "C_P2INCH"))
    )
    (comp (ref "C2")
      (value "100n")
      (footprint "eagle-import:CAP_P2INCH")
      (libsource (lib "eagle-import") (part "C_P2INCH"))
    )
    (comp (ref "C3")
      (value "100n")
      (footprint "eagle-import:CAP_P2INCH")
      (libsource (lib "eagle-import") (part "C_P2INCH"))
    )
    (comp (ref "C4")
      (value "100n")
      (footprint "eagle-import:CAP_P2INCH")
      (libsource (lib "eagle-import") (part "C_P2INCH"))
    )
    (comp (ref "HOLE1")
      (value "3M_MOUNT_HOLE")
      (footprint "eagle-import:3M_HOLE")
      (libsource (lib "eagle-import") (part "3M_MOUNT_HOLE"))
    )
    (comp (ref "HOLE2")
      (value "3M_MOUNT_HOLE")
      (footprint "eagle-import:3M_HOLE")
      (libsource (lib "eagle-import") (part "3M_MOUNT_HOLE"))
    )
    (comp (ref "HOLE3")
      (value "3M_MOUNT_HOLE")
      (footprint "eagle-import:3M_HOLE")
      (libsource (lib "eagle-import") (part "3M_MOUNT_HOLE"))
    )
    (comp (ref "HOLE4")
      (value "3M_MOUNT_HOLE")
      (footprint "eagle-import:3M_HOLE")
      (libsource (lib "eagle-import") (part "3M_MOUNT_HOLE"))
    )
    (comp (ref "TP3")
      (value "TEST_LOOP")
      (footprint "eagle-import:TEST_LOOP")
      (libsource (lib "eagle-import") (part "TEST_LOOP"))
    )
    (comp (ref "TP4")
      (value "TEST_LOOP")
      (footprint "eagle-import:TEST_LOOP")
      (libsource (lib "eagle-import") (part "TEST_LOOP"))
    )
  )
  (nets
    (net (code "1") (name "+5V") (class "Default")
      (node (ref "C1") (pin "1") (pinfunction "1_1") (pintype "passive"))
      (node (ref "C2") (pin "1") (pinfunction "1_1") (pintype "passive"))
      (node (ref "C3") (pin "1") (pinfunction "1_1") (pintype "passive"))
      (node (ref "C4") (pin "1") (pinfunction "1_1") (pintype "passive"))
      (node (ref "D1") (pin "A") (pinfunction "A_A") (pintype "passive"))
      (node (ref "D10") (pin "A") (pinfunction "A_A") (pintype "passive"))
      (node (ref "D11") (pin "A") (pinfunction "A_A") (pintype "passive"))
      (node (ref "D12") (pin "A") (pinfunction "A_A") (pintype "passive"))
      (node (ref "D13") (pin "A") (pinfunction "A_A") (pintype "passive"))
      (node (ref "D14") (pin "A") (pinfunction "A_A") (pintype "passive"))
      (node (ref "D15") (pin "A") (pinfunction "A_A") (pintype "passive"))
      (node (ref "D16") (pin "A") (pinfunction "A_A") (pintype "passive"))
      (node (ref "D17") (pin "A") (pinfunction "A_A") (pintype "passive"))
      (node (ref "D18") (pin "A") (pinfunction "A_A") (pintype "passive"))
      (node (ref "D19") (pin "A") (pinfunction "A_A") (pintype "passive"))
      (node (ref "D2") (pin "A") (pinfunction "A_A") (pintype "passive"))
      (node (ref "D20") (pin "A") (pinfunction "A_A") (pintype "passive"))
      (node (ref "D21") (pin "A") (pinfunction "A_A") (pintype "passive"))
      (node (ref "D22") (pin "A") (pinfunction "A_A") (pintype "passive"))
      (node (ref "D23") (pin "A") (pinfunction "A_A") (pintype "passive"))
      (node (ref "D24") (pin "A") (pinfunction "A_A") (pintype "passive"))
      (node (ref "D25") (pin "A") (pinfunction "A_A") (pintype "passive"))
      (node (ref "D26") (pin "A") (pinfunction "A_A") (pintype "passive"))
      (node (ref "D27") (pin "A") (pinfunction "A_A") (pintype "passive"))
      (node (ref "D28") (pin "A") (pinfunction "A_A") (pintype "passive"))
      (node (ref "D29") (pin "A") (pinfunction "A_A") (pintype "passive"))
      (node (ref "D3") (pin "A") (pinfunction "A_A") (pintype "passive"))
      (node (ref "D30") (pin "A") (pinfunction "A_A") (pintype "passive"))
      (node (ref "D31") (pin "A") (pinfunction "A_A") (pintype "passive"))
      (node (ref "D32") (pin "A") (pinfunction "A_A") (pintype "passive"))
      (node (ref "D33") (pin "A") (pinfunction "A_A") (pintype "passive"))
      (node (ref "D4") (pin "A") (pinfunction "A_A") (pintype "passive"))
      (node (ref "D5") (pin "A") (pinfunction "A_A") (pintype "passive"))
      (node (ref "D6") (pin "A") (pinfunction "A_A") (pintype "passive"))
      (node (ref "D7") (pin "A") (pinfunction "A_A") (pintype "passive"))
      (node (ref "D8") (pin "A") (pinfunction "A_A") (pintype "passive"))
      (node (ref "D9") (pin "A") (pinfunction "A_A") (pintype "passive"))
      (node (ref "R1") (pin "2") (pinfunction "2_2") (pintype "passive"))
      (node (ref "R11") (pin "2") (pinfunction "2_2") (pintype "passive"))
      (node (ref "R13") (pin "2") (pinfunction "2_2") (pintype "passive"))
      (node (ref "R14") (pin "2") (pinfunction "2_2") (pintype "passive"))
      (node (ref "R17") (pin "2") (pinfunction "2_2") (pintype "passive"))
      (node (ref "R18") (pin "2") (pinfunction "2_2") (pintype "passive"))
      (node (ref "R19") (pin "2") (pinfunction "2_2") (pintype "passive"))
      (node (ref "R21") (pin "2") (pinfunction "2_2") (pintype "passive"))
      (node (ref "R23") (pin "2") (pinfunction "2_2") (pintype "passive"))
      (node (ref "R25") (pin "2") (pinfunction "2_2") (pintype "passive"))
      (node (ref "R26") (pin "2") (pinfunction "2_2") (pintype "passive"))
      (node (ref "R29") (pin "2") (pinfunction "2_2") (pintype "passive"))
      (node (ref "R3") (pin "2") (pinfunction "2_2") (pintype "passive"))
      (node (ref "R31") (pin "2") (pinfunction "2_2") (pintype "passive"))
      (node (ref "R33") (pin "2") (pinfunction "2_2") (pintype "passive"))
      (node (ref "R34") (pin "2") (pinfunction "2_2") (pintype "passive"))
      (node (ref "R37") (pin "2") (pinfunction "2_2") (pintype "passive"))
      (node (ref "R39") (pin "2") (pinfunction "2_2") (pintype "passive"))
      (node (ref "R41") (pin "2") (pinfunction "2_2") (pintype "passive"))
      (node (ref "R42") (pin "2") (pinfunction "2_2") (pintype "passive"))
      (node (ref "R45") (pin "2") (pinfunction "2_2") (pintype "passive"))
      (node (ref "R47") (pin "2") (pinfunction "2_2") (pintype "passive"))
      (node (ref "R49") (pin "2") (pinfunction "2_2") (pintype "passive"))
      (node (ref "R5") (pin "2") (pinfunction "2_2") (pintype "passive"))
      (node (ref "R50") (pin "2") (pinfunction "2_2") (pintype "passive"))
      (node (ref "R53") (pin "2") (pinfunction "2_2") (pintype "passive"))
      (node (ref "R55") (pin "2") (pinfunction "2_2") (pintype "passive"))
      (node (ref "R57") (pin "2") (pinfunction "2_2") (pintype "passive"))
      (node (ref "R58") (pin "2") (pinfunction "2_2") (pintype "passive"))
      (node (ref "R6") (pin "2") (pinfunction "2_2") (pintype "passive"))
      (node (ref "R61") (pin "2") (pinfunction "2_2") (pintype "passive"))
      (node (ref "R63") (pin "2") (pinfunction "2_2") (pintype "passive"))
      (node (ref "R65") (pin "2") (pinfunction "2_2") (pintype "passive"))
      (node (ref "R66") (pin "2") (pinfunction "2_2") (pintype "passive"))
      (node (ref "R9") (pin "2") (pinfunction "2_2") (pintype "passive"))
      (node (ref "TP3") (pin "P$1") (pinfunction "P$1_P$1") (pintype "bidirectional"))
    )
    (net (code "2") (name "A0") (class "Default")
      (node (ref "Q1") (pin "G") (pinfunction "G_G") (pintype "passive"))
      (node (ref "TP1") (pin "P$1") (pinfunction "P$1_P$1") (pintype "bidirectional"))
    )
    (net (code "3") (name "A0_AND_B0") (class "Default")
      (node (ref "Q11") (pin "G") (pinfunction "G_G") (pintype "passive"))
      (node (ref "Q3") (pin "D") (pinfunction "D_D") (pintype "passive"))
      (node (ref "Q4") (pin "D") (pinfunction "D_D") (pintype "passive"))
      (node (ref "Q5") (pin "G") (pinfunction "G_G") (pintype "passive"))
      (node (ref "R5") (pin "1") (pinfunction "1_1") (pintype "passive"))
    )
    (net (code "4") (name "A0_AND_B0_N") (class "Default")
      (node (ref "Q5") (pin "D") (pinfunction "D_D") (pintype "passive"))
      (node (ref "R6") (pin "1") (pinfunction "1_1") (pintype "passive"))
      (node (ref "R7") (pin "1") (pinfunction "1_1") (pintype "passive"))
      (node (ref "R8") (pin "1") (pinfunction "1_1") (pintype "passive"))
    )
    (net (code "5") (name "A1") (class "Default")
      (node (ref "Q6") (pin "G") (pinfunction "G_G") (pintype "passive"))
      (node (ref "TP5") (pin "P$1") (pinfunction "P$1_P$1") (pintype "bidirectional"))
    )
    (net (code "6") (name "A1_AND_B1") (class "Default")
      (node (ref "Q10") (pin "G") (pinfunction "G_G") (pintype "passive"))
      (node (ref "Q12") (pin "G") (pinfunction "G_G") (pintype "passive"))
      (node (ref "Q8") (pin "D") (pinfunction "D_D") (pintype "passive"))
      (node (ref "Q9") (pin "D") (pinfunction "D_D") (pintype "passive"))
      (node (ref "R13") (pin "1") (pinfunction "1_1") (pintype "passive"))
    )
    (net (code "7") (name "A1_AND_B1_N") (class "Default")
      (node (ref "Q10") (pin "D") (pinfunction "D_D") (pintype "passive"))
      (node (ref "R14") (pin "1") (pinfunction "1_1") (pintype "passive"))
      (node (ref "R15") (pin "1") (pinfunction "1_1") (pintype "passive"))
      (node (ref "R16") (pin "1") (pinfunction "1_1") (pintype "passive"))
    )
    (net (code "8") (name "A2") (class "Default")
      (node (ref "Q15") (pin "G") (pinfunction "G_G") (pintype "passive"))
      (node (ref "TP9") (pin "P$1") (pinfunction "P$1_P$1") (pintype "bidirectional"))
    )
    (net (code "9") (name "A2_AND_B2") (class "Default")
      (node (ref "Q17") (pin "D") (pinfunction "D_D") (pintype "passive"))
      (node (ref "Q18") (pin "D") (pinfunction "D_D") (pintype "passive"))
      (node (ref "Q19") (pin "G") (pinfunction "G_G") (pintype "passive"))
      (node (ref "Q25") (pin "G") (pinfunction "G_G") (pintype "passive"))
      (node (ref "R25") (pin "1") (pinfunction "1_1") (pintype "passive"))
    )
    (net (code "10") (name "A2_AND_B2_N") (class "Default")
      (node (ref "Q19") (pin "D") (pinfunction "D_D") (pintype "passive"))
      (node (ref "R26") (pin "1") (pinfunction "1_1") (pintype "passive"))
      (node (ref "R27") (pin "1") (pinfunction "1_1") (pintype "passive"))
      (node (ref "R28") (pin "1") (pinfunction "1_1") (pintype "passive"))
    )
    (net (code "11") (name "A3") (class "Default")
      (node (ref "Q20") (pin "G") (pinfunction "G_G") (pintype "passive"))
      (node (ref "TP11") (pin "P$1") (pinfunction "P$1_P$1") (pintype "bidirectional"))
    )
    (net (code "12") (name "A3_AND_B3") (class "Default")
      (node (ref "Q22") (pin "D") (pinfunction "D_D") (pintype "passive"))
      (node (ref "Q23") (pin "D") (pinfunction "D_D") (pintype "passive"))
      (node (ref "Q24") (pin "G") (pinfunction "G_G") (pintype "passive"))
      (node (ref "Q26") (pin "G") (pinfunction "G_G") (pintype "passive"))
      (node (ref "R33") (pin "1") (pinfunction "1_1") (pintype "passive"))
    )
    (net (code "13") (name "A3_AND_B3_N") (class "Default")
      (node (ref "Q24") (pin "D") (pinfunction "D_D") (pintype "passive"))
      (node (ref "R34") (pin "1") (pinfunction "1_1") (pintype "passive"))
      (node (ref "R35") (pin "1") (pinfunction "1_1") (pintype "passive"))
      (node (ref "R36") (pin "1") (pinfunction "1_1") (pintype "passive"))
    )
    (net (code "14") (name "A4") (class "Default")
      (node (ref "Q27") (pin "G") (pinfunction "G_G") (pintype "passive"))
      (node (ref "TP13") (pin "P$1") (pinfunction "P$1_P$1") (pintype "bidirectional"))
    )
    (net (code "15") (name "A4_AND_B4") (class "Default")
      (node (ref "Q29") (pin "D") (pinfunction "D_D") (pintype "passive"))
      (node (ref "Q30") (pin "D") (pinfunction "D_D") (pintype "passive"))
      (node (ref "Q31") (pin "G") (pinfunction "G_G") (pintype "passive"))
      (node (ref "Q47") (pin "G") (pinfunction "G_G") (pintype "passive"))
      (node (ref "R41") (pin "1") (pinfunction "1_1") (pintype "passive"))
    )
    (net (code "16") (name "A4_AND_B4_N") (class "Default")
      (node (ref "Q31") (pin "D") (pinfunction "D_D") (pintype "passive"))
      (node (ref "R42") (pin "1") (pinfunction "1_1") (pintype "passive"))
      (node (ref "R43") (pin "1") (pinfunction "1_1") (pintype "passive"))
      (node (ref "R44") (pin "1") (pinfunction "1_1") (pintype "passive"))
    )
    (net (code "17") (name "A5") (class "Default")
      (node (ref "Q32") (pin "G") (pinfunction "G_G") (pintype "passive"))
      (node (ref "TP15") (pin "P$1") (pinfunction "P$1_P$1") (pintype "bidirectional"))
    )
    (net (code "18") (name "A5_AND_B5") (class "Default")
      (node (ref "Q34") (pin "D") (pinfunction "D_D") (pintype "passive"))
      (node (ref "Q35") (pin "D") (pinfunction "D_D") (pintype "passive"))
      (node (ref "Q36") (pin "G") (pinfunction "G_G") (pintype "passive"))
      (node (ref "Q48") (pin "G") (pinfunction "G_G") (pintype "passive"))
      (node (ref "R49") (pin "1") (pinfunction "1_1") (pintype "passive"))
    )
    (net (code "19") (name "A5_AND_B5_N") (class "Default")
      (node (ref "Q36") (pin "D") (pinfunction "D_D") (pintype "passive"))
      (node (ref "R50") (pin "1") (pinfunction "1_1") (pintype "passive"))
      (node (ref "R51") (pin "1") (pinfunction "1_1") (pintype "passive"))
      (node (ref "R52") (pin "1") (pinfunction "1_1") (pintype "passive"))
    )
    (net (code "20") (name "A6") (class "Default")
      (node (ref "Q37") (pin "G") (pinfunction "G_G") (pintype "passive"))
      (node (ref "TP17") (pin "P$1") (pinfunction "P$1_P$1") (pintype "bidirectional"))
    )
    (net (code "21") (name "A6_AND_B6") (class "Default")
      (node (ref "Q39") (pin "D") (pinfunction "D_D") (pintype "passive"))
      (node (ref "Q40") (pin "D") (pinfunction "D_D") (pintype "passive"))
      (node (ref "Q41") (pin "G") (pinfunction "G_G") (pintype "passive"))
      (node (ref "Q49") (pin "G") (pinfunction "G_G") (pintype "passive"))
      (node (ref "R57") (pin "1") (pinfunction "1_1") (pintype "passive"))
    )
    (net (code "22") (name "A6_AND_B6_N") (class "Default")
      (node (ref "Q41") (pin "D") (pinfunction "D_D") (pintype "passive"))
      (node (ref "R58") (pin "1") (pinfunction "1_1") (pintype "passive"))
      (node (ref "R59") (pin "1") (pinfunction "1_1") (pintype "passive"))
      (node (ref "R60") (pin "1") (pinfunction "1_1") (pintype "passive"))
    )
    (net (code "23") (name "A7") (class "Default")
      (node (ref "Q42") (pin "G") (pinfunction "G_G") (pintype "passive"))
      (node (ref "TP19") (pin "P$1") (pinfunction "P$1_P$1") (pintype "bidirectional"))
    )
    (net (code "24") (name "A7_AND_B7") (class "Default")
      (node (ref "Q44") (pin "D") (pinfunction "D_D") (pintype "passive"))
      (node (ref "Q45") (pin "D") (pinfunction "D_D") (pintype "passive"))
      (node (ref "Q46") (pin "G") (pinfunction "G_G") (pintype "passive"))
      (node (ref "Q50") (pin "G") (pinfunction "G_G") (pintype "passive"))
      (node (ref "R65") (pin "1") (pinfunction "1_1") (pintype "passive"))
    )
    (net (code "25") (name "A7_AND_B7_N") (class "Default")
      (node (ref "Q46") (pin "D") (pinfunction "D_D") (pintype "passive"))
      (node (ref "R66") (pin "1") (pinfunction "1_1") (pintype "passive"))
      (node (ref "R67") (pin "1") (pinfunction "1_1") (pintype "passive"))
      (node (ref "R68") (pin "1") (pinfunction "1_1") (pintype "passive"))
    )
    (net (code "26") (name "B0") (class "Default")
      (node (ref "Q2") (pin "G") (pinfunction "G_G") (pintype "passive"))
      (node (ref "TP2") (pin "P$1") (pinfunction "P$1_P$1") (pintype "bidirectional"))
    )
    (net (code "27") (name "B1") (class "Default")
      (node (ref "Q7") (pin "G") (pinfunction "G_G") (pintype "passive"))
      (node (ref "TP6") (pin "P$1") (pinfunction "P$1_P$1") (pintype "bidirectional"))
    )
    (net (code "28") (name "B2") (class "Default")
      (node (ref "Q16") (pin "G") (pinfunction "G_G") (pintype "passive"))
      (node (ref "TP10") (pin "P$1") (pinfunction "P$1_P$1") (pintype "bidirectional"))
    )
    (net (code "29") (name "B3") (class "Default")
      (node (ref "Q21") (pin "G") (pinfunction "G_G") (pintype "passive"))
      (node (ref "TP12") (pin "P$1") (pinfunction "P$1_P$1") (pintype "bidirectional"))
    )
    (net (code "30") (name "B4") (class "Default")
      (node (ref "Q28") (pin "G") (pinfunction "G_G") (pintype "passive"))
      (node (ref "TP14") (pin "P$1") (pinfunction "P$1_P$1") (pintype "bidirectional"))
    )
    (net (code "31") (name "B5") (class "Default")
      (node (ref "Q33") (pin "G") (pinfunction "G_G") (pintype "passive"))
      (node (ref "TP16") (pin "P$1") (pinfunction "P$1_P$1") (pintype "bidirectional"))
    )
    (net (code "32") (name "B6") (class "Default")
      (node (ref "Q38") (pin "G") (pinfunction "G_G") (pintype "passive"))
      (node (ref "TP18") (pin "P$1") (pinfunction "P$1_P$1") (pintype "bidirectional"))
    )
    (net (code "33") (name "B7") (class "Default")
      (node (ref "Q43") (pin "G") (pinfunction "G_G") (pintype "passive"))
      (node (ref "TP20") (pin "P$1") (pinfunction "P$1_P$1") (pintype "bidirectional"))
    )
    (net (code "34") (name "GND") (class "Default")
      (node (ref "C1") (pin "2") (pinfunction "2_2") (pintype "passive"))
      (node (ref "C2") (pin "2") (pinfunction "2_2") (pintype "passive"))
      (node (ref "C3") (pin "2") (pinfunction "2_2") (pintype "passive"))
      (node (ref "C4") (pin "2") (pinfunction "2_2") (pintype "passive"))
      (node (ref "Q1") (pin "S") (pinfunction "S_S") (pintype "passive"))
      (node (ref "Q10") (pin "S") (pinfunction "S_S") (pintype "passive"))
      (node (ref "Q11") (pin "S") (pinfunction "S_S") (pintype "passive"))
      (node (ref "Q12") (pin "S") (pinfunction "S_S") (pintype "passive"))
      (node (ref "Q13") (pin "S") (pinfunction "S_S") (pintype "passive"))
      (node (ref "Q14") (pin "S") (pinfunction "S_S") (pintype "passive"))
      (node (ref "Q15") (pin "S") (pinfunction "S_S") (pintype "passive"))
      (node (ref "Q16") (pin "S") (pinfunction "S_S") (pintype "passive"))
      (node (ref "Q17") (pin "S") (pinfunction "S_S") (pintype "passive"))
      (node (ref "Q18") (pin "S") (pinfunction "S_S") (pintype "passive"))
      (node (ref "Q19") (pin "S") (pinfunction "S_S") (pintype "passive"))
      (node (ref "Q2") (pin "S") (pinfunction "S_S") (pintype "passive"))
      (node (ref "Q20") (pin "S") (pinfunction "S_S") (pintype "passive"))
      (node (ref "Q21") (pin "S") (pinfunction "S_S") (pintype "passive"))
      (node (ref "Q22") (pin "S") (pinfunction "S_S") (pintype "passive"))
      (node (ref "Q23") (pin "S") (pinfunction "S_S") (pintype "passive"))
      (node (ref "Q24") (pin "S") (pinfunction "S_S") (pintype "passive"))
      (node (ref "Q25") (pin "S") (pinfunction "S_S") (pintype "passive"))
      (node (ref "Q26") (pin "S") (pinfunction "S_S") (pintype "passive"))
      (node (ref "Q27") (pin "S") (pinfunction "S_S") (pintype "passive"))
      (node (ref "Q28") (pin "S") (pinfunction "S_S") (pintype "passive"))
      (node (ref "Q29") (pin "S") (pinfunction "S_S") (pintype "passive"))
      (node (ref "Q3") (pin "S") (pinfunction "S_S") (pintype "passive"))
      (node (ref "Q30") (pin "S") (pinfunction "S_S") (pintype "passive"))
      (node (ref "Q31") (pin "S") (pinfunction "S_S") (pintype "passive"))
      (node (ref "Q32") (pin "S") (pinfunction "S_S") (pintype "passive"))
      (node (ref "Q33") (pin "S") (pinfunction "S_S") (pintype "passive"))
      (node (ref "Q34") (pin "S") (pinfunction "S_S") (pintype "passive"))
      (node (ref "Q35") (pin "S") (pinfunction "S_S") (pintype "passive"))
      (node (ref "Q36") (pin "S") (pinfunction "S_S") (pintype "passive"))
      (node (ref "Q37") (pin "S") (pinfunction "S_S") (pintype "passive"))
      (node (ref "Q38") (pin "S") (pinfunction "S_S") (pintype "passive"))
      (node (ref "Q39") (pin "S") (pinfunction "S_S") (pintype "passive"))
      (node (ref "Q4") (pin "S") (pinfunction "S_S") (pintype "passive"))
      (node (ref "Q40") (pin "S") (pinfunction "S_S") (pintype "passive"))
      (node (ref "Q41") (pin "S") (pinfunction "S_S") (pintype "passive"))
      (node (ref "Q42") (pin "S") (pinfunction "S_S") (pintype "passive"))
      (node (ref "Q43") (pin "S") (pinfunction "S_S") (pintype "passive"))
      (node (ref "Q44") (pin "S") (pinfunction "S_S") (pintype "passive"))
      (node (ref "Q45") (pin "S") (pinfunction "S_S") (pintype "passive"))
      (node (ref "Q46") (pin "S") (pinfunction "S_S") (pintype "passive"))
      (node (ref "Q47") (pin "S") (pinfunction "S_S") (pintype "passive"))
      (node (ref "Q48") (pin "S") (pinfunction "S_S") (pintype "passive"))
      (node (ref "Q49") (pin "S") (pinfunction "S_S") (pintype "passive"))
      (node (ref "Q5") (pin "S") (pinfunction "S_S") (pintype "passive"))
      (node (ref "Q50") (pin "S") (pinfunction "S_S") (pintype "passive"))
      (node (ref "Q6") (pin "S") (pinfunction "S_S") (pintype "passive"))
      (node (ref "Q7") (pin "S") (pinfunction "S_S") (pintype "passive"))
      (node (ref "Q8") (pin "S") (pinfunction "S_S") (pintype "passive"))
      (node (ref "Q9") (pin "S") (pinfunction "S_S") (pintype "passive"))
      (node (ref "TP4") (pin "P$1") (pinfunction "P$1_P$1") (pintype "bidirectional"))
    )
    (net (code "35") (name "Net-(D1-C)") (class "Default")
      (node (ref "D1") (pin "K") (pinfunction "C_K") (pintype "passive"))
      (node (ref "R2") (pin "2") (pinfunction "2_2") (pintype "passive"))
    )
    (net (code "36") (name "Net-(D2-C)") (class "Default")
      (node (ref "D2") (pin "K") (pinfunction "C_K") (pintype "passive"))
      (node (ref "R4") (pin "2") (pinfunction "2_2") (pintype "passive"))
    )
    (net (code "37") (name "Net-(D3-C)") (class "Default")
      (node (ref "D3") (pin "K") (pinfunction "C_K") (pintype "passive"))
      (node (ref "R7") (pin "2") (pinfunction "2_2") (pintype "passive"))
    )
    (net (code "38") (name "Net-(D4-C)") (class "Default")
      (node (ref "D4") (pin "K") (pinfunction "C_K") (pintype "passive"))
      (node (ref "R8") (pin "2") (pinfunction "2_2") (pintype "passive"))
    )
    (net (code "39") (name "Net-(D5-C)") (class "Default")
      (node (ref "D5") (pin "K") (pinfunction "C_K") (pintype "passive"))
      (node (ref "R10") (pin "2") (pinfunction "2_2") (pintype "passive"))
    )
    (net (code "40") (name "Net-(D6-C)") (class "Default")
      (node (ref "D6") (pin "K") (pinfunction "C_K") (pintype "passive"))
      (node (ref "R12") (pin "2") (pinfunction "2_2") (pintype "passive"))
    )
    (net (code "41") (name "Net-(D7-C)") (class "Default")
      (node (ref "D7") (pin "K") (pinfunction "C_K") (pintype "passive"))
      (node (ref "R15") (pin "2") (pinfunction "2_2") (pintype "passive"))
    )
    (net (code "42") (name "Net-(D8-C)") (class "Default")
      (node (ref "D8") (pin "K") (pinfunction "C_K") (pintype "passive"))
      (node (ref "R16") (pin "2") (pinfunction "2_2") (pintype "passive"))
    )
    (net (code "43") (name "Net-(D9-C)") (class "Default")
      (node (ref "D9") (pin "K") (pinfunction "C_K") (pintype "passive"))
      (node (ref "R20") (pin "2") (pinfunction "2_2") (pintype "passive"))
    )
    (net (code "44") (name "Net-(D10-C)") (class "Default")
      (node (ref "D10") (pin "K") (pinfunction "C_K") (pintype "passive"))
      (node (ref "R22") (pin "2") (pinfunction "2_2") (pintype "passive"))
    )
    (net (code "45") (name "Net-(D11-C)") (class "Default")
      (node (ref "D11") (pin "K") (pinfunction "C_K") (pintype "passive"))
      (node (ref "R24") (pin "2") (pinfunction "2_2") (pintype "passive"))
    )
    (net (code "46") (name "Net-(D12-C)") (class "Default")
      (node (ref "D12") (pin "K") (pinfunction "C_K") (pintype "passive"))
      (node (ref "R27") (pin "2") (pinfunction "2_2") (pintype "passive"))
    )
    (net (code "47") (name "Net-(D13-C)") (class "Default")
      (node (ref "D13") (pin "K") (pinfunction "C_K") (pintype "passive"))
      (node (ref "R28") (pin "2") (pinfunction "2_2") (pintype "passive"))
    )
    (net (code "48") (name "Net-(D14-C)") (class "Default")
      (node (ref "D14") (pin "K") (pinfunction "C_K") (pintype "passive"))
      (node (ref "R30") (pin "2") (pinfunction "2_2") (pintype "passive"))
    )
    (net (code "49") (name "Net-(D15-C)") (class "Default")
      (node (ref "D15") (pin "K") (pinfunction "C_K") (pintype "passive"))
      (node (ref "R32") (pin "2") (pinfunction "2_2") (pintype "passive"))
    )
    (net (code "50") (name "Net-(D16-C)") (class "Default")
      (node (ref "D16") (pin "K") (pinfunction "C_K") (pintype "passive"))
      (node (ref "R35") (pin "2") (pinfunction "2_2") (pintype "passive"))
    )
    (net (code "51") (name "Net-(D17-C)") (class "Default")
      (node (ref "D17") (pin "K") (pinfunction "C_K") (pintype "passive"))
      (node (ref "R36") (pin "2") (pinfunction "2_2") (pintype "passive"))
    )
    (net (code "52") (name "Net-(D18-C)") (class "Default")
      (node (ref "D18") (pin "K") (pinfunction "C_K") (pintype "passive"))
      (node (ref "R38") (pin "2") (pinfunction "2_2") (pintype "passive"))
    )
    (net (code "53") (name "Net-(D19-C)") (class "Default")
      (node (ref "D19") (pin "K") (pinfunction "C_K") (pintype "passive"))
      (node (ref "R40") (pin "2") (pinfunction "2_2") (pintype "passive"))
    )
    (net (code "54") (name "Net-(D20-C)") (class "Default")
      (node (ref "D20") (pin "K") (pinfunction "C_K") (pintype "passive"))
      (node (ref "R43") (pin "2") (pinfunction "2_2") (pintype "passive"))
    )
    (net (code "55") (name "Net-(D21-C)") (class "Default")
      (node (ref "D21") (pin "K") (pinfunction "C_K") (pintype "passive"))
      (node (ref "R44") (pin "2") (pinfunction "2_2") (pintype "passive"))
    )
    (net (code "56") (name "Net-(D22-C)") (class "Default")
      (node (ref "D22") (pin "K") (pinfunction "C_K") (pintype "passive"))
      (node (ref "R46") (pin "2") (pinfunction "2_2") (pintype "passive"))
    )
    (net (code "57") (name "Net-(D23-C)") (class "Default")
      (node (ref "D23") (pin "K") (pinfunction "C_K") (pintype "passive"))
      (node (ref "R48") (pin "2") (pinfunction "2_2") (pintype "passive"))
    )
    (net (code "58") (name "Net-(D24-C)") (class "Default")
      (node (ref "D24") (pin "K") (pinfunction "C_K") (pintype "passive"))
      (node (ref "R51") (pin "2") (pinfunction "2_2") (pintype "passive"))
    )
    (net (code "59") (name "Net-(D25-C)") (class "Default")
      (node (ref "D25") (pin "K") (pinfunction "C_K") (pintype "passive"))
      (node (ref "R52") (pin "2") (pinfunction "2_2") (pintype "passive"))
    )
    (net (code "60") (name "Net-(D26-C)") (class "Default")
      (node (ref "D26") (pin "K") (pinfunction "C_K") (pintype "passive"))
      (node (ref "R54") (pin "2") (pinfunction "2_2") (pintype "passive"))
    )
    (net (code "61") (name "Net-(D27-C)") (class "Default")
      (node (ref "D27") (pin "K") (pinfunction "C_K") (pintype "passive"))
      (node (ref "R56") (pin "2") (pinfunction "2_2") (pintype "passive"))
    )
    (net (code "62") (name "Net-(D28-C)") (class "Default")
      (node (ref "D28") (pin "K") (pinfunction "C_K") (pintype "passive"))
      (node (ref "R59") (pin "2") (pinfunction "2_2") (pintype "passive"))
    )
    (net (code "63") (name "Net-(D29-C)") (class "Default")
      (node (ref "D29") (pin "K") (pinfunction "C_K") (pintype "passive"))
      (node (ref "R60") (pin "2") (pinfunction "2_2") (pintype "passive"))
    )
    (net (code "64") (name "Net-(D30-C)") (class "Default")
      (node (ref "D30") (pin "K") (pinfunction "C_K") (pintype "passive"))
      (node (ref "R62") (pin "2") (pinfunction "2_2") (pintype "passive"))
    )
    (net (code "65") (name "Net-(D31-C)") (class "Default")
      (node (ref "D31") (pin "K") (pinfunction "C_K") (pintype "passive"))
      (node (ref "R64") (pin "2") (pinfunction "2_2") (pintype "passive"))
    )
    (net (code "66") (name "Net-(D32-C)") (class "Default")
      (node (ref "D32") (pin "K") (pinfunction "C_K") (pintype "passive"))
      (node (ref "R67") (pin "2") (pinfunction "2_2") (pintype "passive"))
    )
    (net (code "67") (name "Net-(D33-C)") (class "Default")
      (node (ref "D33") (pin "K") (pinfunction "C_K") (pintype "passive"))
      (node (ref "R68") (pin "2") (pinfunction "2_2") (pintype "passive"))
    )
    (net (code "68") (name "Net-(Q1-PadD)") (class "Default")
      (node (ref "Q1") (pin "D") (pinfunction "D_D") (pintype "passive"))
      (node (ref "Q3") (pin "G") (pinfunction "G_G") (pintype "passive"))
      (node (ref "R1") (pin "1") (pinfunction "1_1") (pintype "passive"))
      (node (ref "R2") (pin "1") (pinfunction "1_1") (pintype "passive"))
    )
    (net (code "69") (name "Net-(Q2-PadD)") (class "Default")
      (node (ref "Q2") (pin "D") (pinfunction "D_D") (pintype "passive"))
      (node (ref "Q4") (pin "G") (pinfunction "G_G") (pintype "passive"))
      (node (ref "R3") (pin "1") (pinfunction "1_1") (pintype "passive"))
      (node (ref "R4") (pin "1") (pinfunction "1_1") (pintype "passive"))
    )
    (net (code "70") (name "Net-(Q6-PadD)") (class "Default")
      (node (ref "Q6") (pin "D") (pinfunction "D_D") (pintype "passive"))
      (node (ref "Q8") (pin "G") (pinfunction "G_G") (pintype "passive"))
      (node (ref "R10") (pin "1") (pinfunction "1_1") (pintype "passive"))
      (node (ref "R9") (pin "1") (pinfunction "1_1") (pintype "passive"))
    )
    (net (code "71") (name "Net-(Q7-PadD)") (class "Default")
      (node (ref "Q7") (pin "D") (pinfunction "D_D") (pintype "passive"))
      (node (ref "Q9") (pin "G") (pinfunction "G_G") (pintype "passive"))
      (node (ref "R11") (pin "1") (pinfunction "1_1") (pintype "passive"))
      (node (ref "R12") (pin "1") (pinfunction "1_1") (pintype "passive"))
    )
    (net (code "72") (name "Net-(Q11-PadD)") (class "Default")
      (node (ref "Q11") (pin "D") (pinfunction "D_D") (pintype "passive"))
      (node (ref "Q12") (pin "D") (pinfunction "D_D") (pintype "passive"))
      (node (ref "Q13") (pin "G") (pinfunction "G_G") (pintype "passive"))
      (node (ref "Q25") (pin "D") (pinfunction "D_D") (pintype "passive"))
      (node (ref "Q26") (pin "D") (pinfunction "D_D") (pintype "passive"))
      (node (ref "Q47") (pin "D") (pinfunction "D_D") (pintype "passive"))
      (node (ref "Q48") (pin "D") (pinfunction "D_D") (pintype "passive"))
      (node (ref "Q49") (pin "D") (pinfunction "D_D") (pintype "passive"))
      (node (ref "Q50") (pin "D") (pinfunction "D_D") (pintype "passive"))
      (node (ref "R17") (pin "1") (pinfunction "1_1") (pintype "passive"))
    )
    (net (code "73") (name "Net-(Q15-PadD)") (class "Default")
      (node (ref "Q15") (pin "D") (pinfunction "D_D") (pintype "passive"))
      (node (ref "Q17") (pin "G") (pinfunction "G_G") (pintype "passive"))
      (node (ref "R21") (pin "1") (pinfunction "1_1") (pintype "passive"))
      (node (ref "R22") (pin "1") (pinfunction "1_1") (pintype "passive"))
    )
    (net (code "74") (name "Net-(Q16-PadD)") (class "Default")
      (node (ref "Q16") (pin "D") (pinfunction "D_D") (pintype "passive"))
      (node (ref "Q18") (pin "G") (pinfunction "G_G") (pintype "passive"))
      (node (ref "R23") (pin "1") (pinfunction "1_1") (pintype "passive"))
      (node (ref "R24") (pin "1") (pinfunction "1_1") (pintype "passive"))
    )
    (net (code "75") (name "Net-(Q20-PadD)") (class "Default")
      (node (ref "Q20") (pin "D") (pinfunction "D_D") (pintype "passive"))
      (node (ref "Q22") (pin "G") (pinfunction "G_G") (pintype "passive"))
      (node (ref "R29") (pin "1") (pinfunction "1_1") (pintype "passive"))
      (node (ref "R30") (pin "1") (pinfunction "1_1") (pintype "passive"))
    )
    (net (code "76") (name "Net-(Q21-PadD)") (class "Default")
      (node (ref "Q21") (pin "D") (pinfunction "D_D") (pintype "passive"))
      (node (ref "Q23") (pin "G") (pinfunction "G_G") (pintype "passive"))
      (node (ref "R31") (pin "1") (pinfunction "1_1") (pintype "passive"))
      (node (ref "R32") (pin "1") (pinfunction "1_1") (pintype "passive"))
    )
    (net (code "77") (name "Net-(Q27-PadD)") (class "Default")
      (node (ref "Q27") (pin "D") (pinfunction "D_D") (pintype "passive"))
      (node (ref "Q29") (pin "G") (pinfunction "G_G") (pintype "passive"))
      (node (ref "R37") (pin "1") (pinfunction "1_1") (pintype "passive"))
      (node (ref "R38") (pin "1") (pinfunction "1_1") (pintype "passive"))
    )
    (net (code "78") (name "Net-(Q28-PadD)") (class "Default")
      (node (ref "Q28") (pin "D") (pinfunction "D_D") (pintype "passive"))
      (node (ref "Q30") (pin "G") (pinfunction "G_G") (pintype "passive"))
      (node (ref "R39") (pin "1") (pinfunction "1_1") (pintype "passive"))
      (node (ref "R40") (pin "1") (pinfunction "1_1") (pintype "passive"))
    )
    (net (code "79") (name "Net-(Q32-PadD)") (class "Default")
      (node (ref "Q32") (pin "D") (pinfunction "D_D") (pintype "passive"))
      (node (ref "Q34") (pin "G") (pinfunction "G_G") (pintype "passive"))
      (node (ref "R45") (pin "1") (pinfunction "1_1") (pintype "passive"))
      (node (ref "R46") (pin "1") (pinfunction "1_1") (pintype "passive"))
    )
    (net (code "80") (name "Net-(Q33-PadD)") (class "Default")
      (node (ref "Q33") (pin "D") (pinfunction "D_D") (pintype "passive"))
      (node (ref "Q35") (pin "G") (pinfunction "G_G") (pintype "passive"))
      (node (ref "R47") (pin "1") (pinfunction "1_1") (pintype "passive"))
      (node (ref "R48") (pin "1") (pinfunction "1_1") (pintype "passive"))
    )
    (net (code "81") (name "Net-(Q37-PadD)") (class "Default")
      (node (ref "Q37") (pin "D") (pinfunction "D_D") (pintype "passive"))
      (node (ref "Q39") (pin "G") (pinfunction "G_G") (pintype "passive"))
      (node (ref "R53") (pin "1") (pinfunction "1_1") (pintype "passive"))
      (node (ref "R54") (pin "1") (pinfunction "1_1") (pintype "passive"))
    )
    (net (code "82") (name "Net-(Q38-PadD)") (class "Default")
      (node (ref "Q38") (pin "D") (pinfunction "D_D") (pintype "passive"))
      (node (ref "Q40") (pin "G") (pinfunction "G_G") (pintype "passive"))
      (node (ref "R55") (pin "1") (pinfunction "1_1") (pintype "passive"))
      (node (ref "R56") (pin "1") (pinfunction "1_1") (pintype "passive"))
    )
    (net (code "83") (name "Net-(Q42-PadD)") (class "Default")
      (node (ref "Q42") (pin "D") (pinfunction "D_D") (pintype "passive"))
      (node (ref "Q44") (pin "G") (pinfunction "G_G") (pintype "passive"))
      (node (ref "R61") (pin "1") (pinfunction "1_1") (pintype "passive"))
      (node (ref "R62") (pin "1") (pinfunction "1_1") (pintype "passive"))
    )
    (net (code "84") (name "Net-(Q43-PadD)") (class "Default")
      (node (ref "Q43") (pin "D") (pinfunction "D_D") (pintype "passive"))
      (node (ref "Q45") (pin "G") (pinfunction "G_G") (pintype "passive"))
      (node (ref "R63") (pin "1") (pinfunction "1_1") (pintype "passive"))
      (node (ref "R64") (pin "1") (pinfunction "1_1") (pintype "passive"))
    )
    (net (code "85") (name "RES") (class "Default")
      (node (ref "Q13") (pin "D") (pinfunction "D_D") (pintype "passive"))
      (node (ref "Q14") (pin "G") (pinfunction "G_G") (pintype "passive"))
      (node (ref "R18") (pin "1") (pinfunction "1_1") (pintype "passive"))
      (node (ref "TP8") (pin "P$1") (pinfunction "P$1_P$1") (pintype "bidirectional"))
    )
    (net (code "86") (name "RES_N") (class "Default")
      (node (ref "Q14") (pin "D") (pinfunction "D_D") (pintype "passive"))
      (node (ref "R19") (pin "1") (pinfunction "1_1") (pintype "passive"))
      (node (ref "R20") (pin "1") (pinfunction "1_1") (pintype "passive"))
      (node (ref "TP7") (pin "P$1") (pinfunction "P$1_P$1") (pintype "bidirectional"))
    )
  )
)
